# FranKinksTides.net
KiCad netlist of a schematic drawn in EAGLE
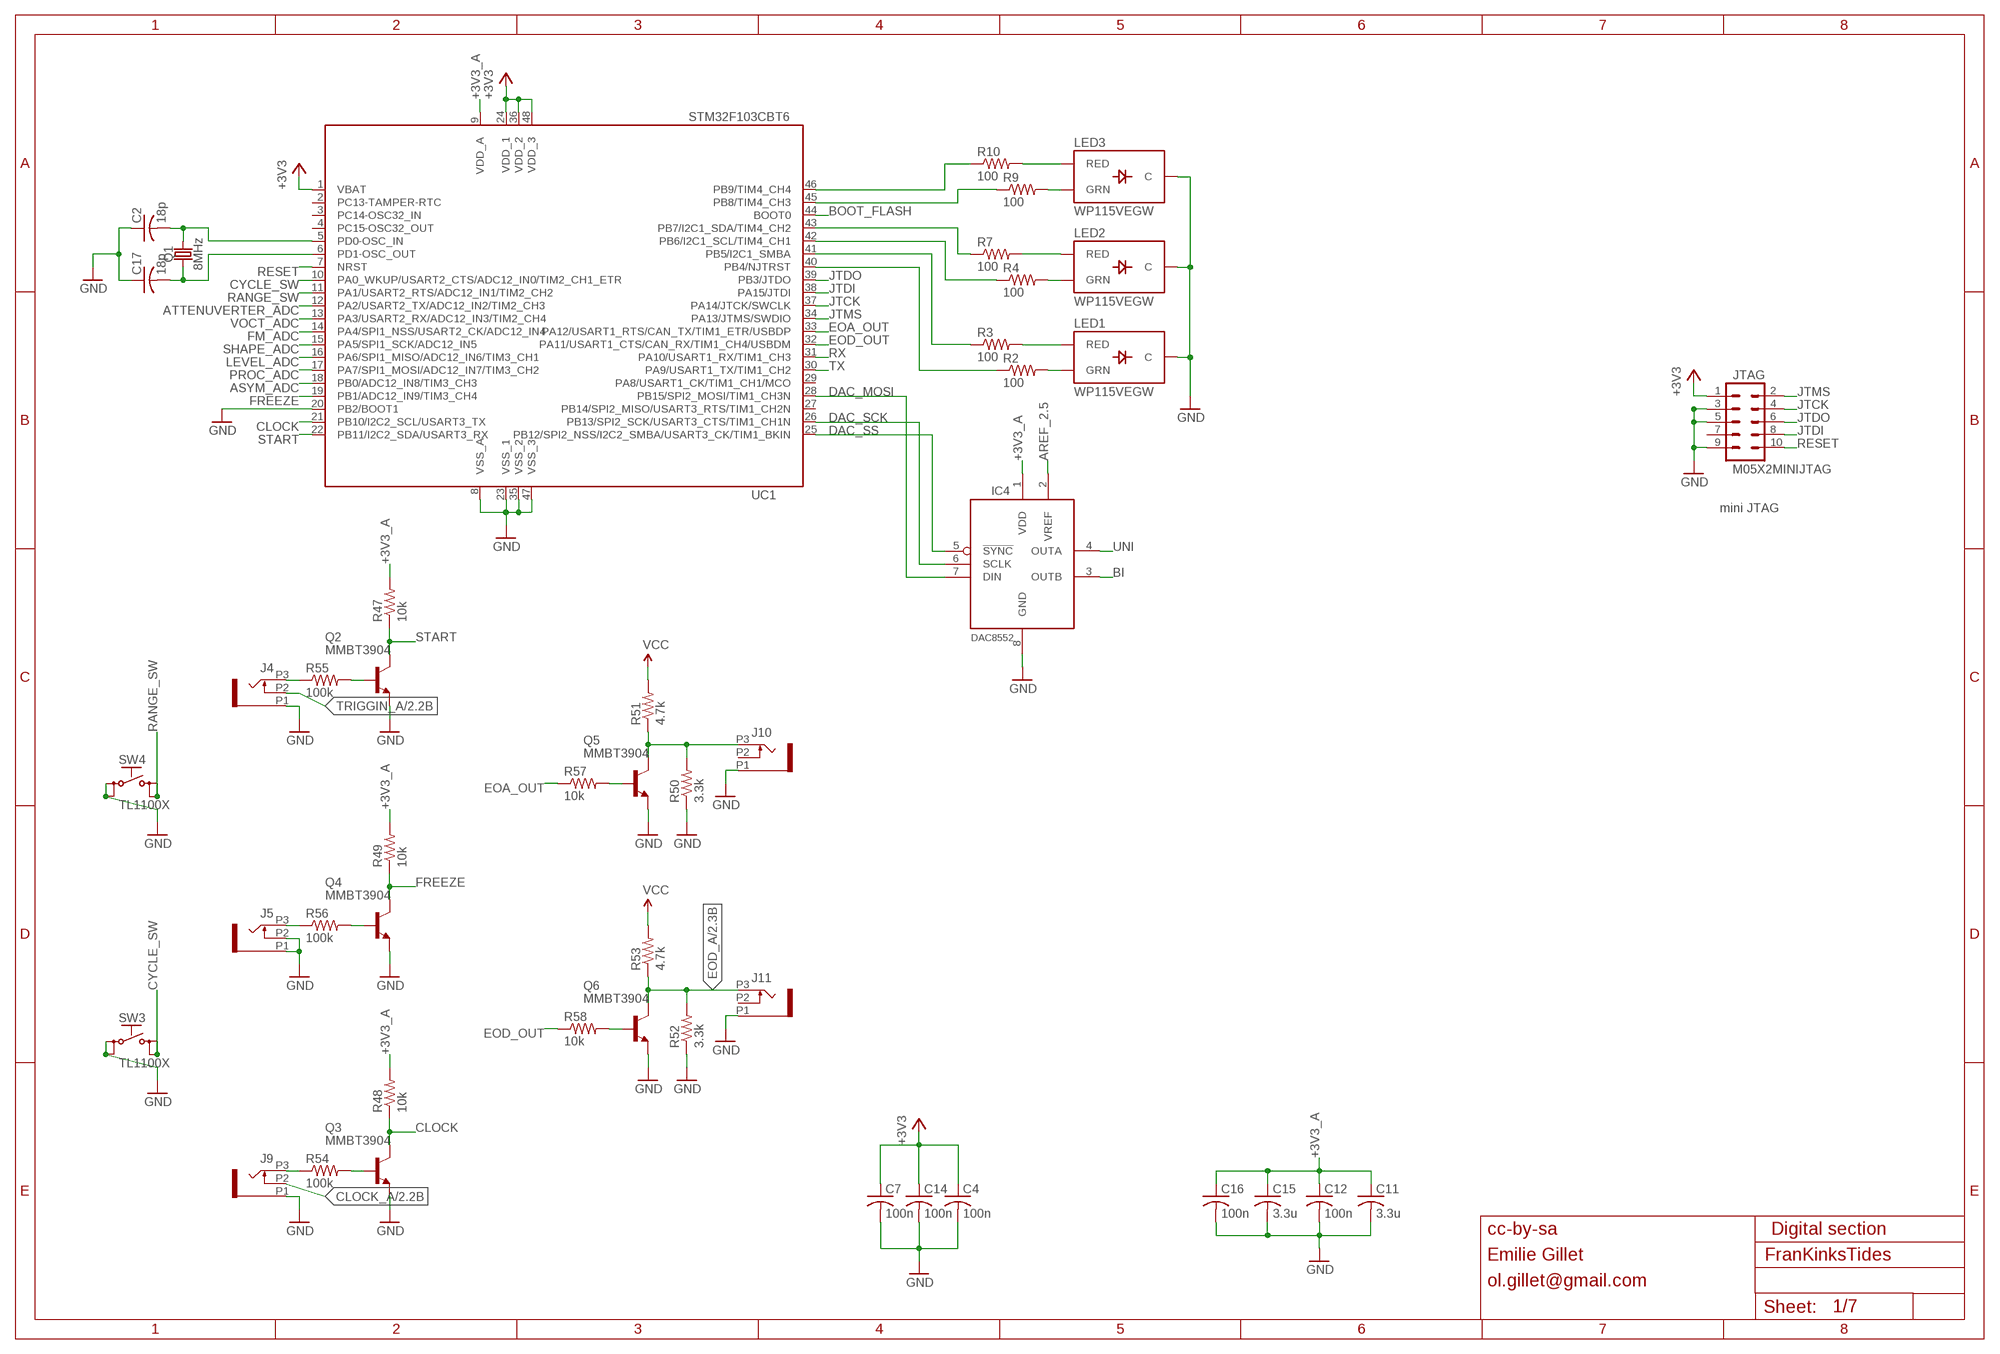
[diagram p0: schematic, sheet 1]
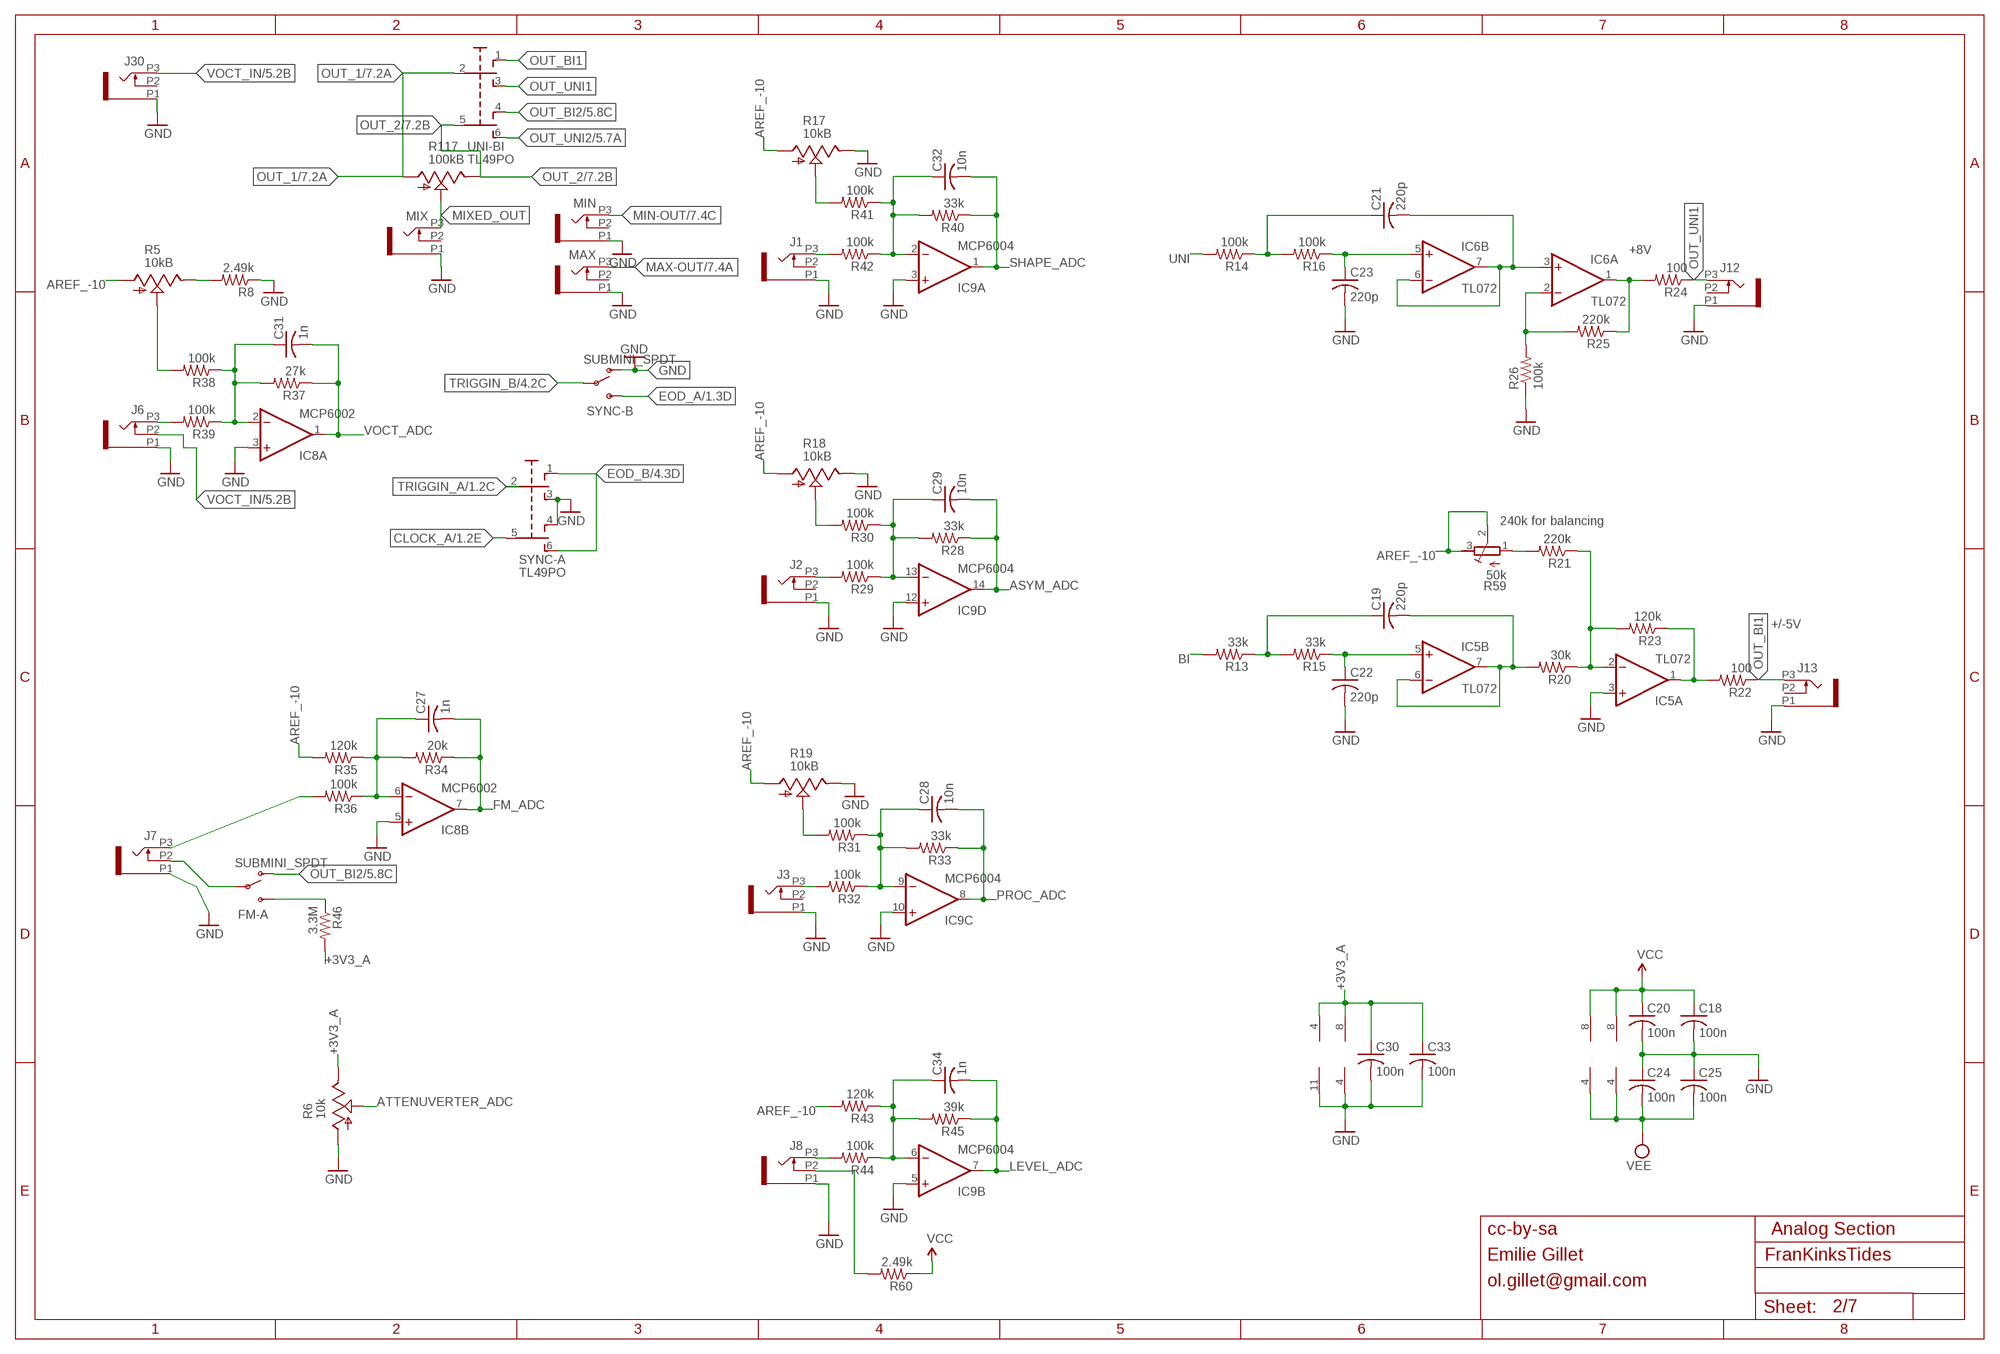
[diagram p1: schematic, sheet 2]
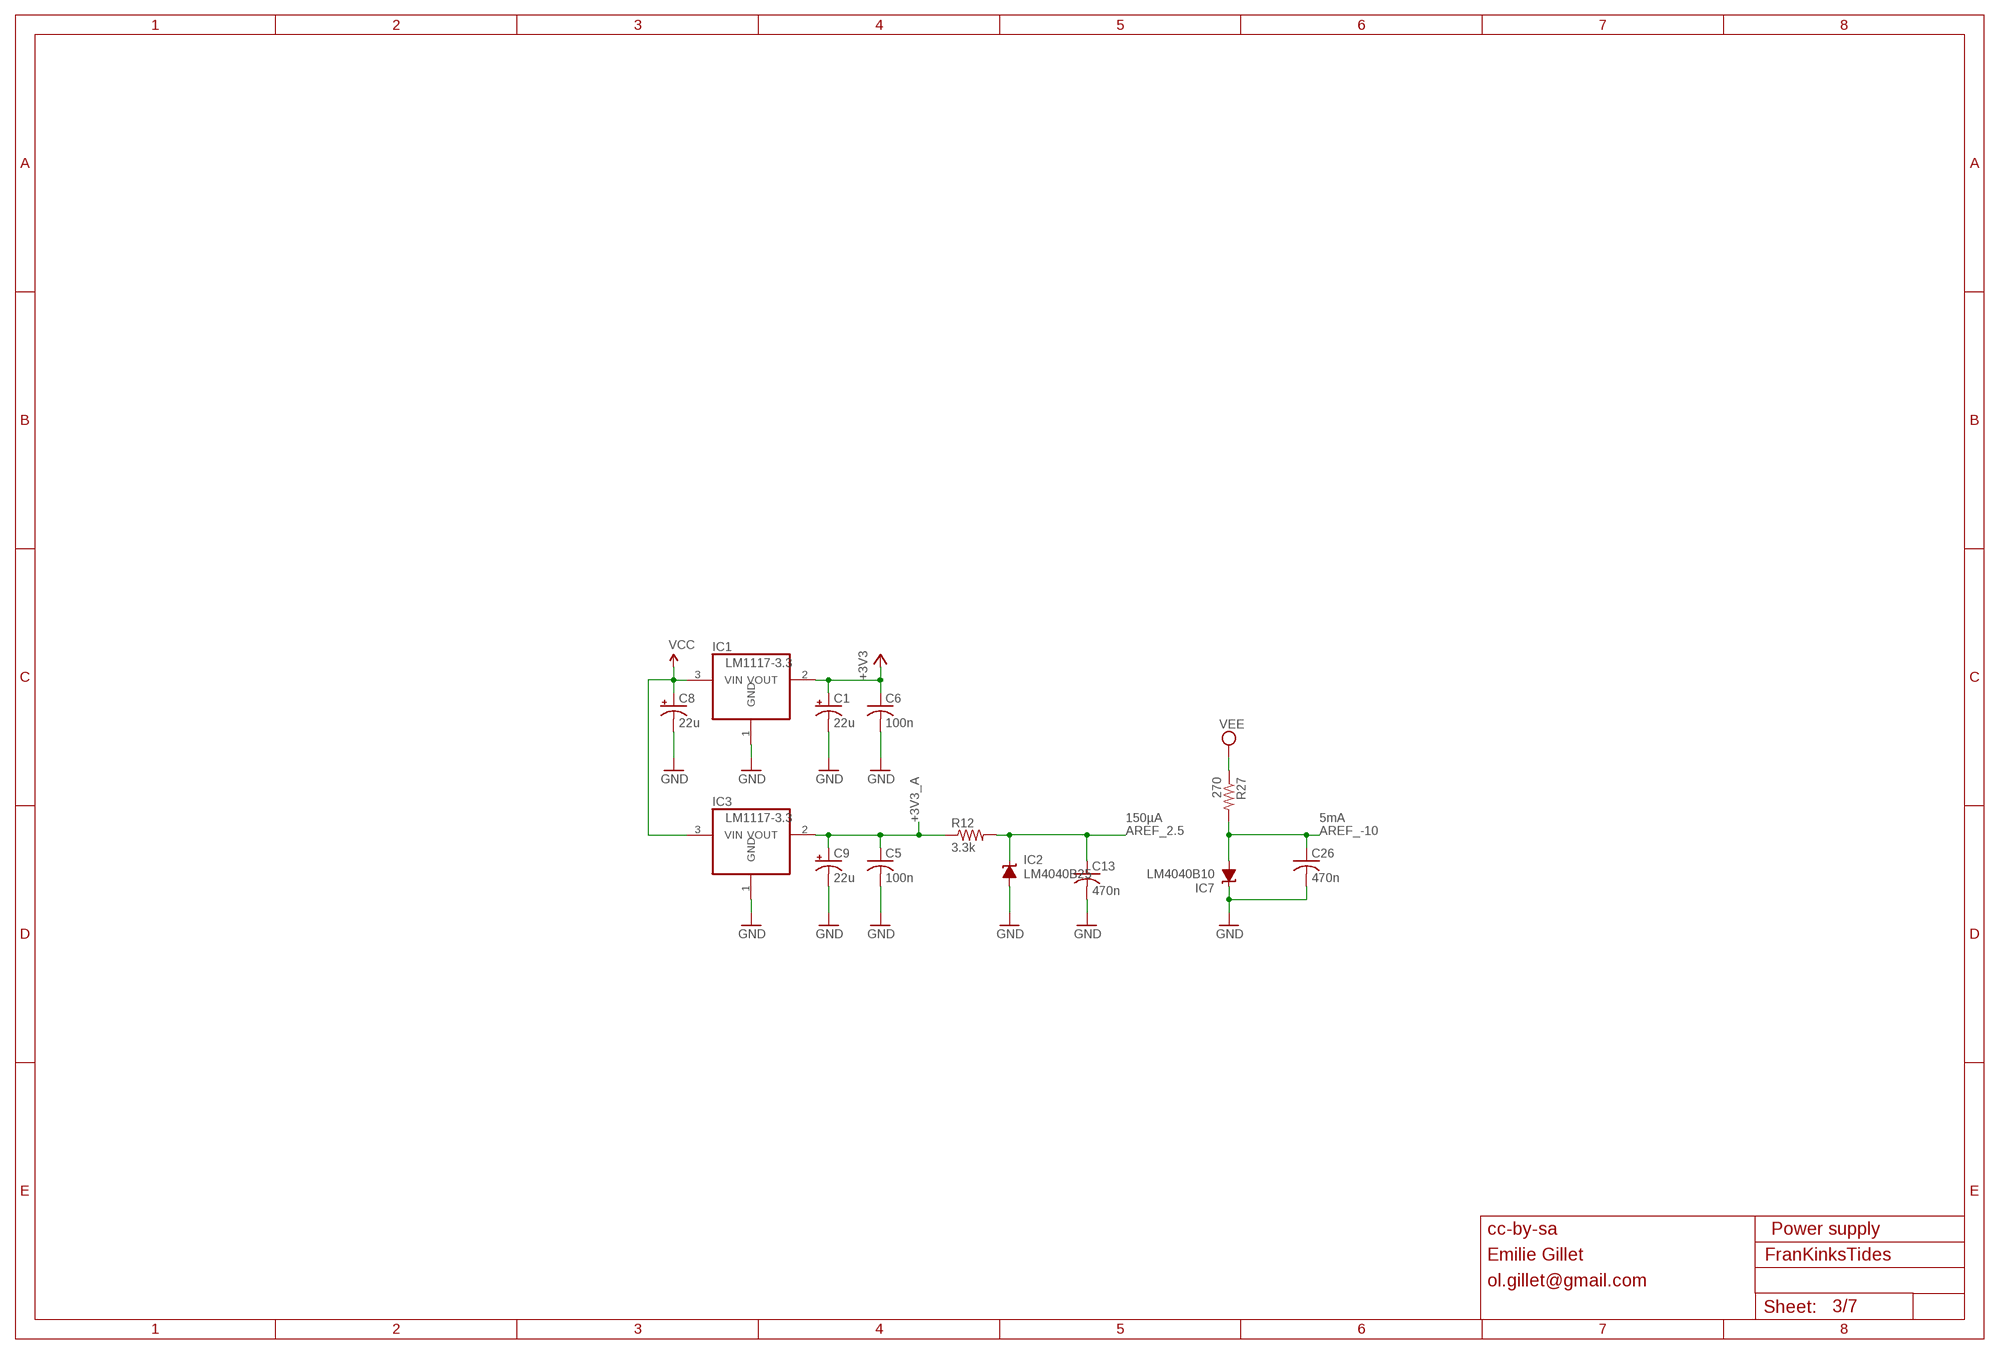
[diagram p2: schematic, sheet 3]
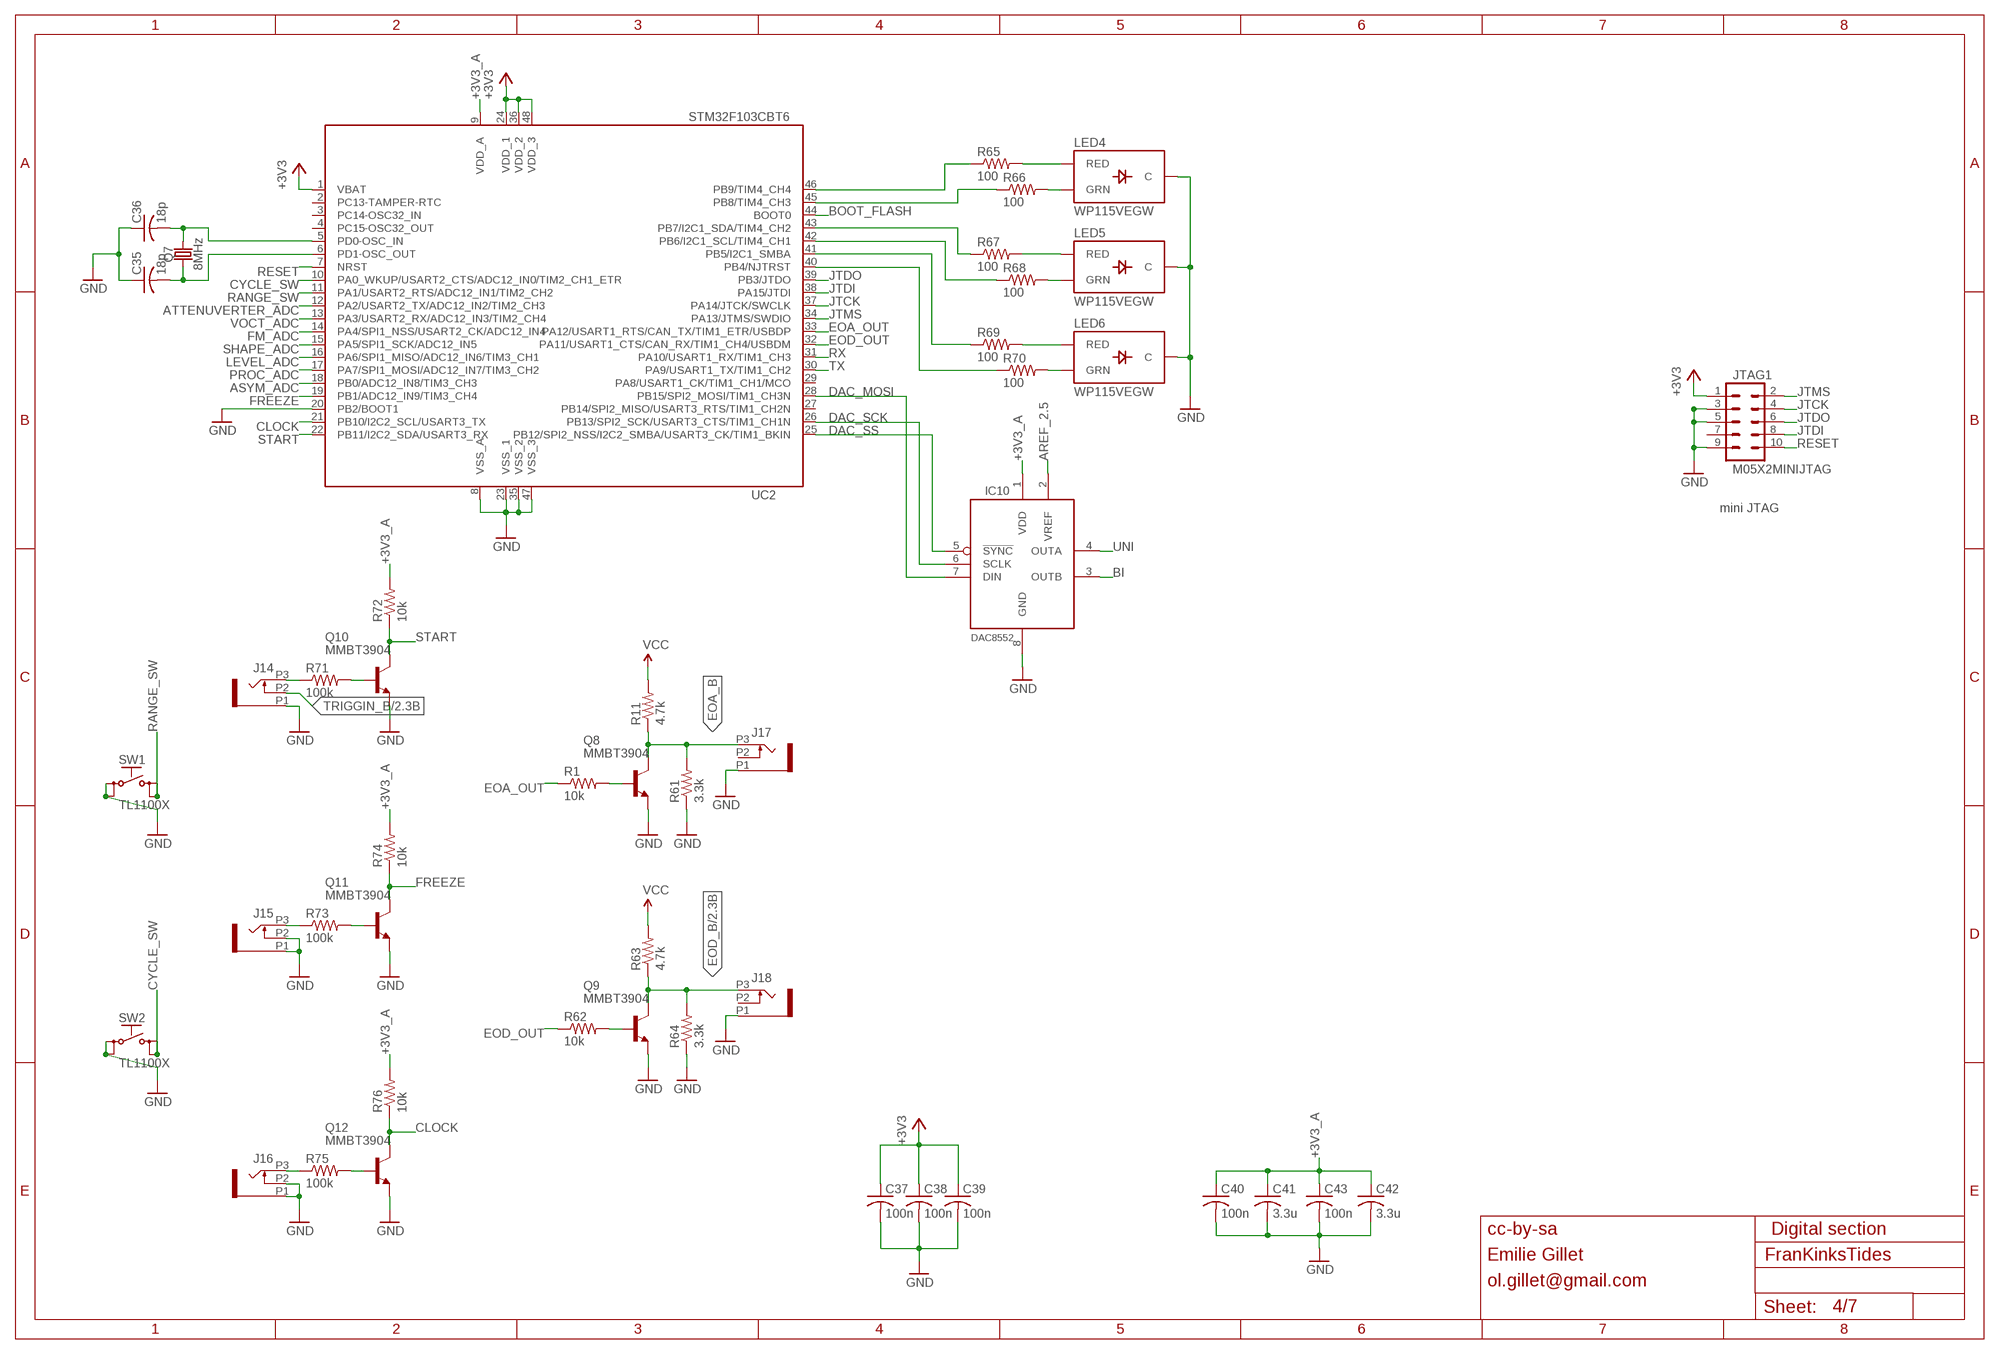
[diagram p3: schematic, sheet 4]
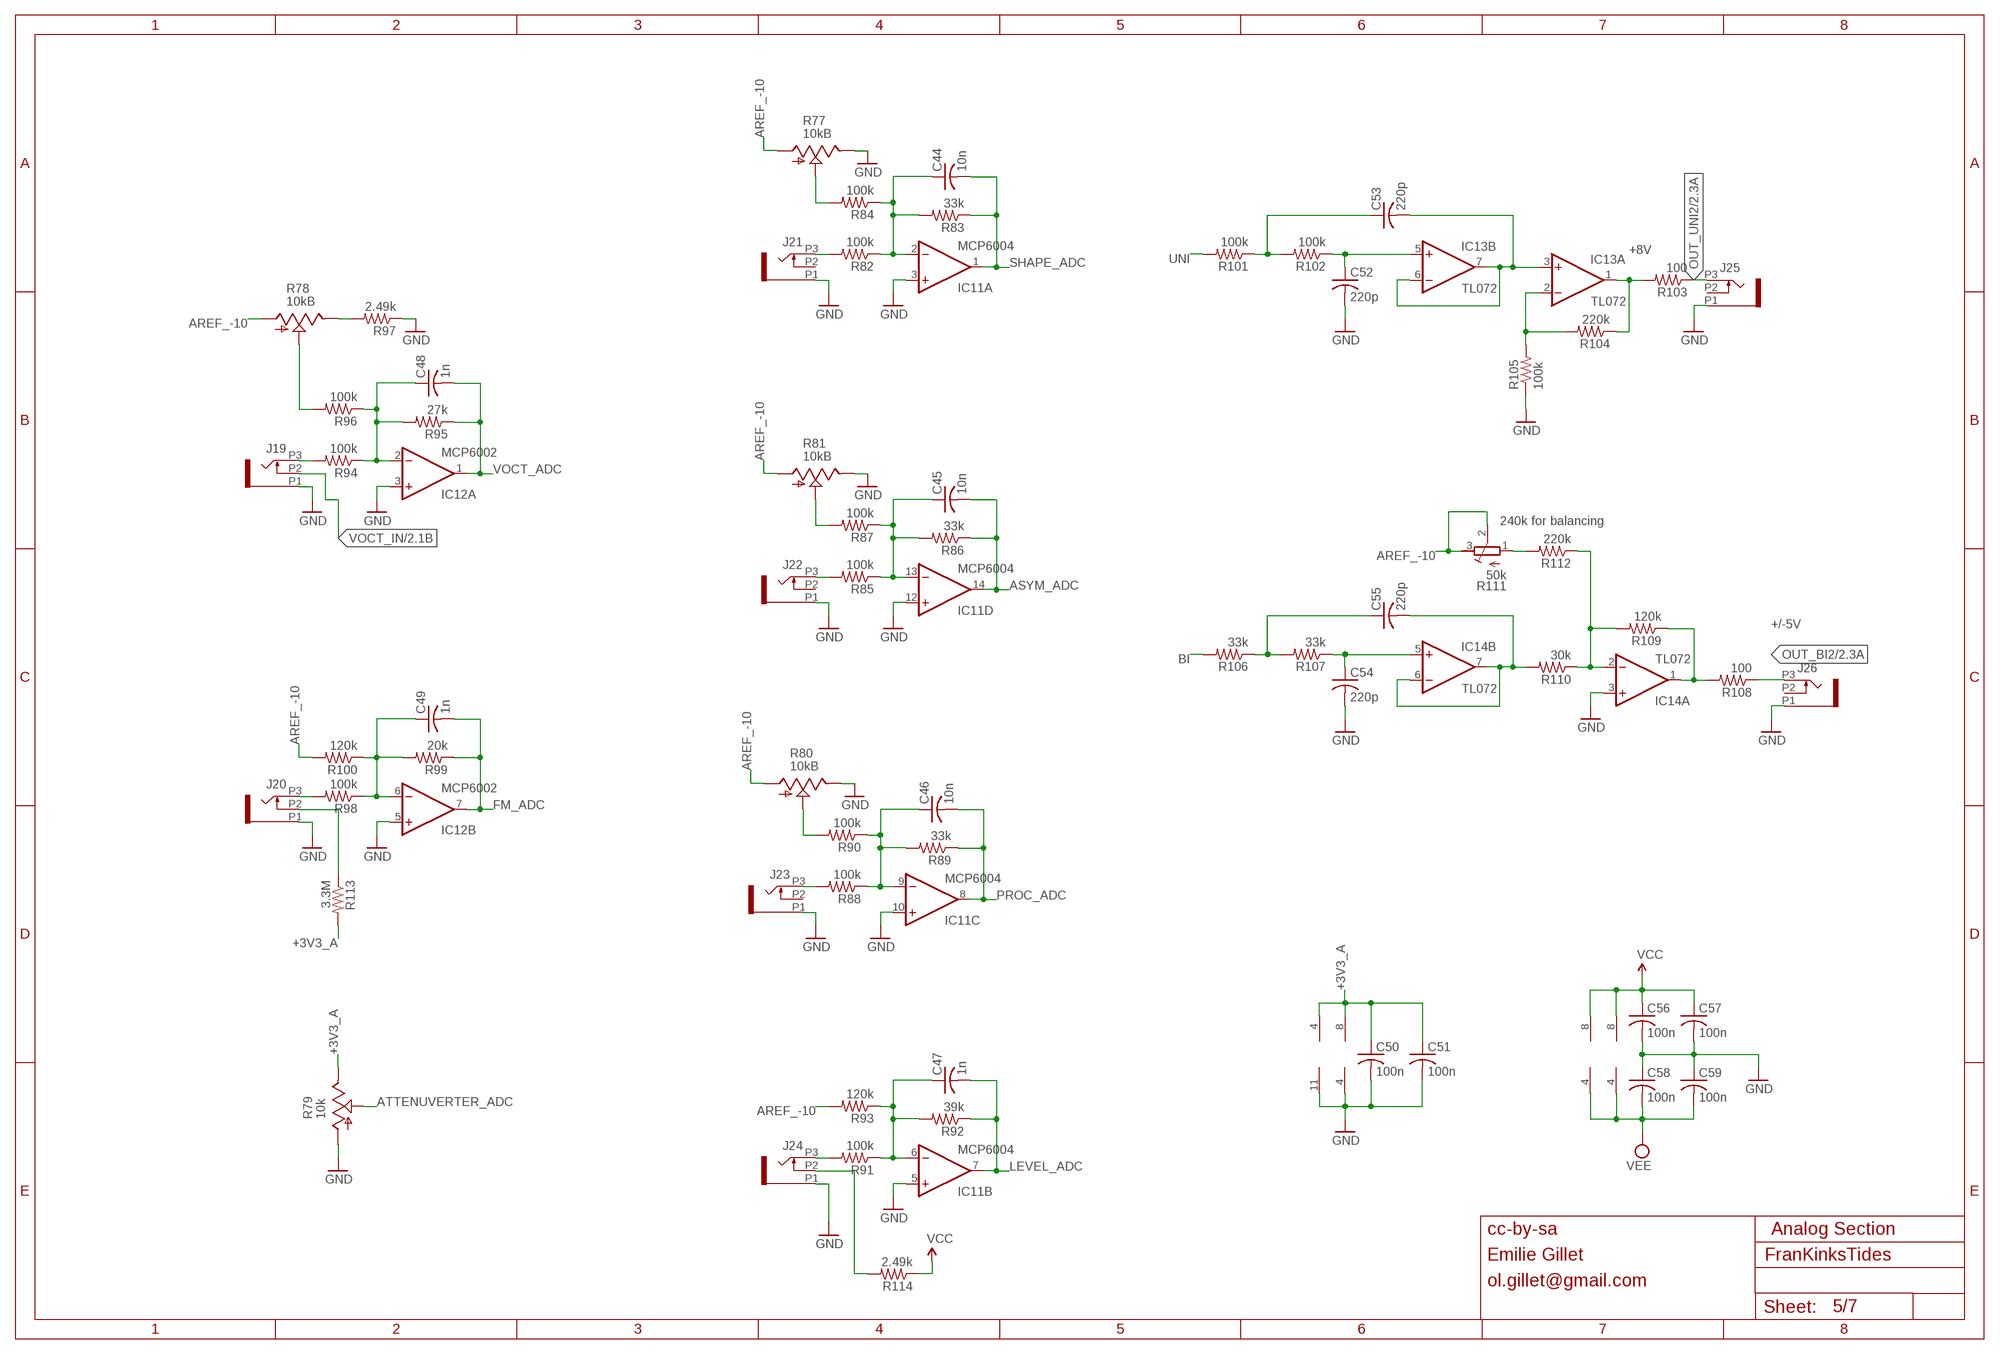
[diagram p4: schematic, sheet 5]
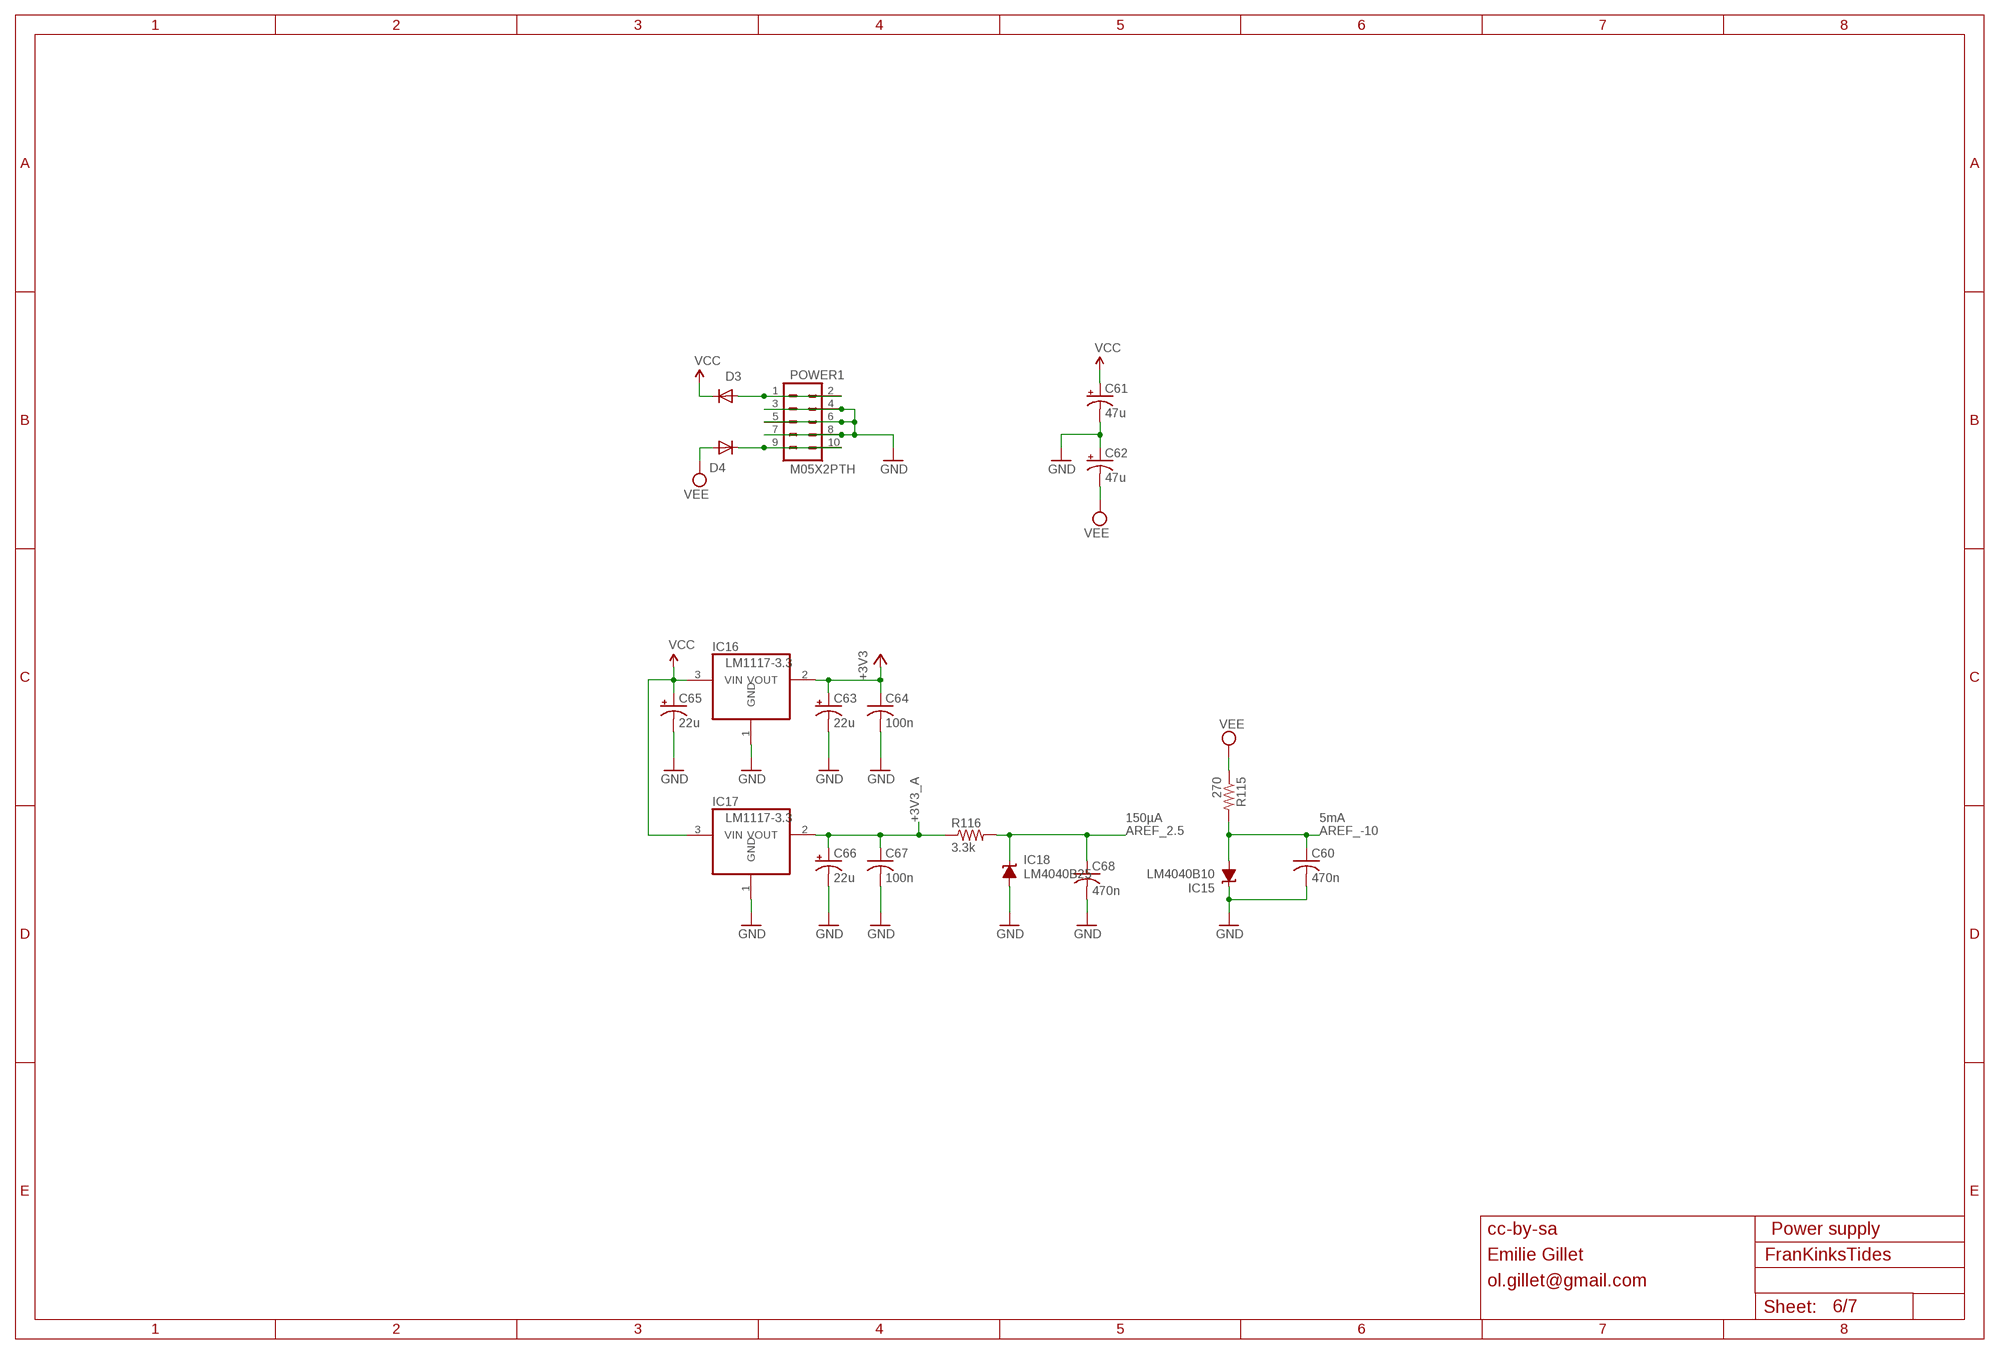
[diagram p5: schematic, sheet 6]
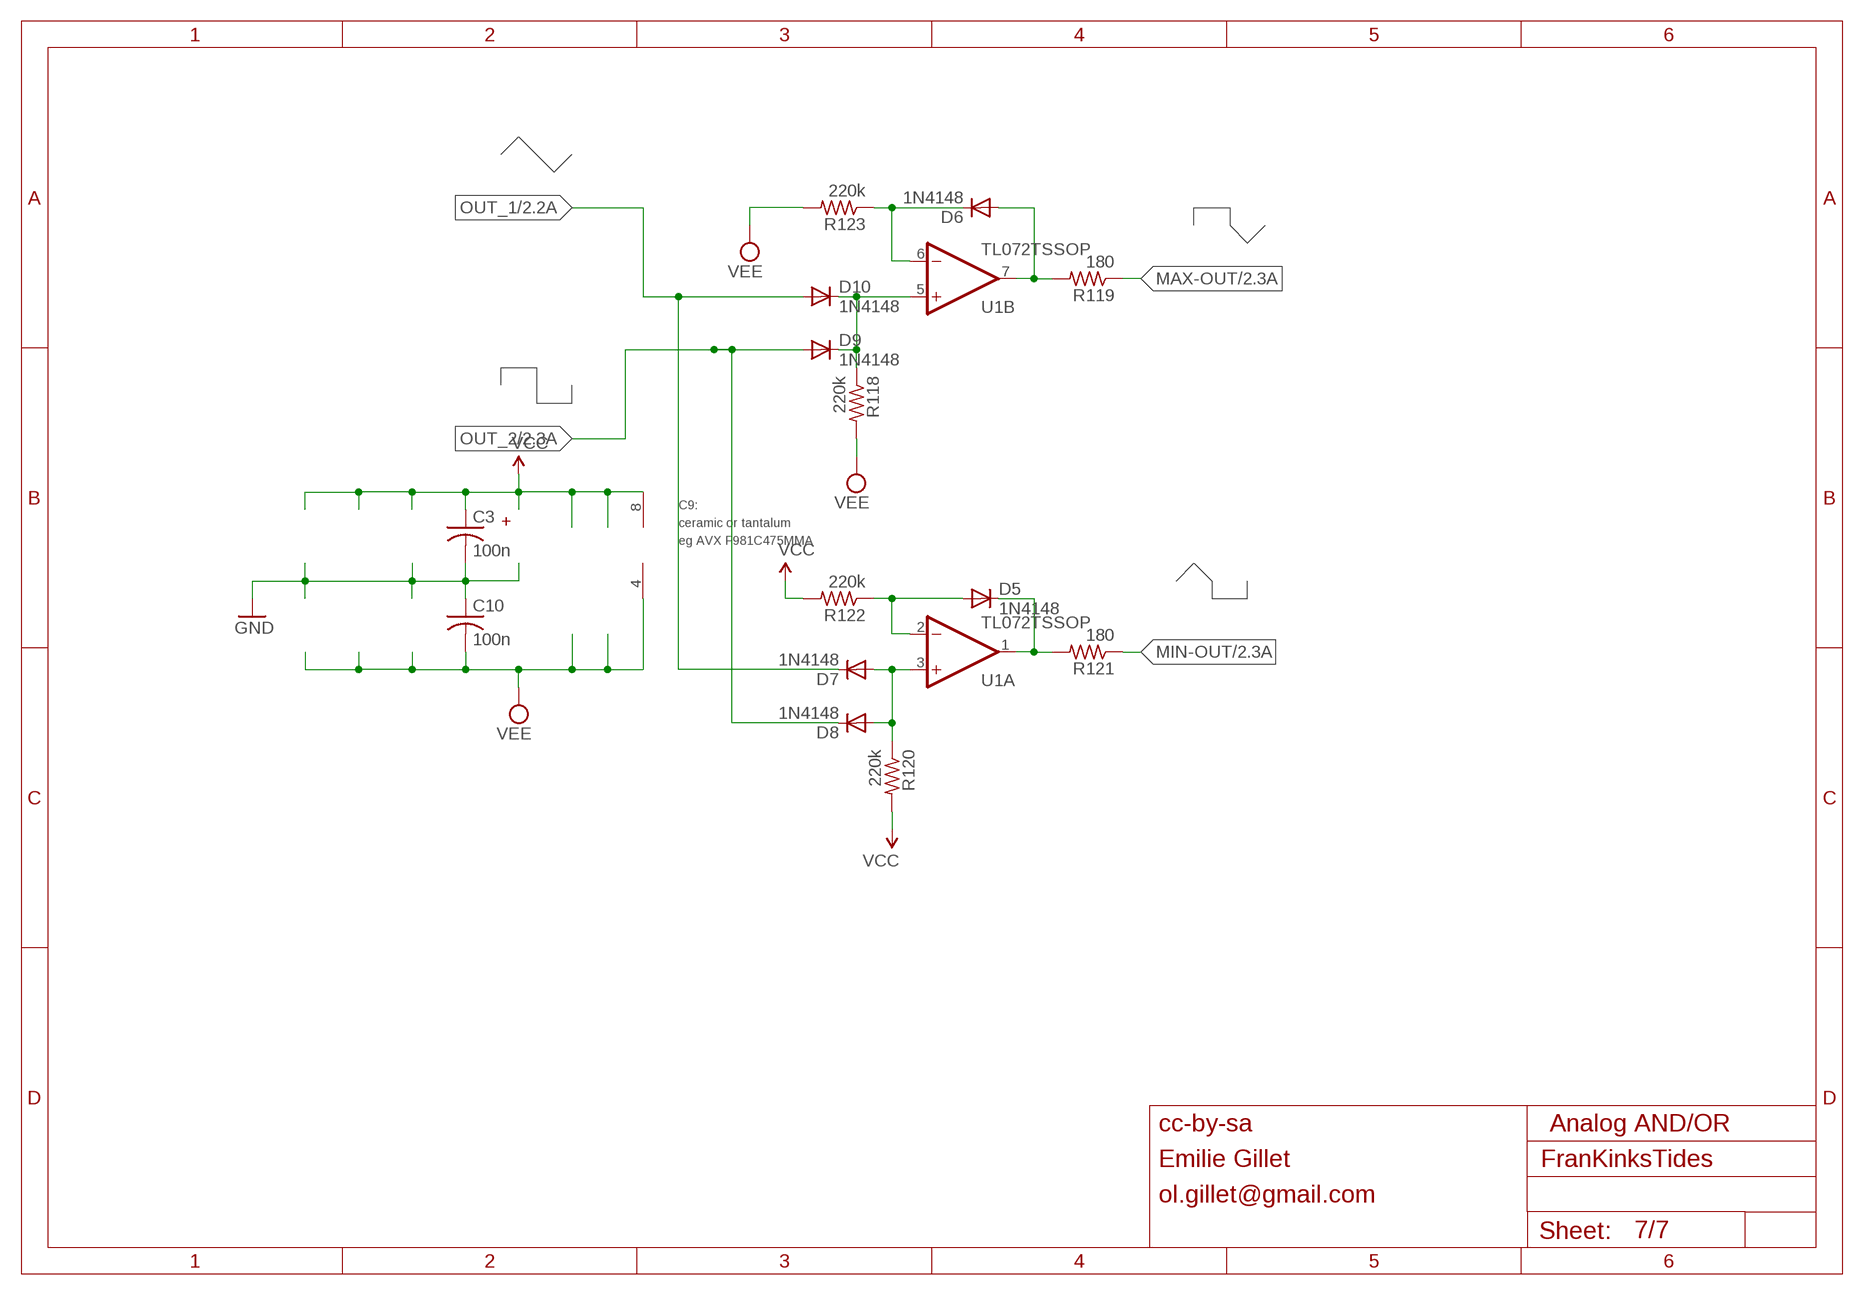
[diagram p6: schematic, sheet 7]

(export (version "E")
  (design (tool "Eeschema 10.0.6"))
  (components
    (comp (ref "C1")
      (value "22u")
      (footprint "eagle-import:PANASONIC_C")
      (libsource (lib "eagle-import") (part "CPOL-USC"))
    )
    (comp (ref "C5")
      (value "100n")
      (footprint "eagle-import:C0603")
      (libsource (lib "eagle-import") (part "C-USC0603"))
    )
    (comp (ref "C6")
      (value "100n")
      (footprint "eagle-import:C0603")
      (libsource (lib "eagle-import") (part "C-USC0603"))
    )
    (comp (ref "C8")
      (value "22u")
      (footprint "eagle-import:PANASONIC_C")
      (libsource (lib "eagle-import") (part "CPOL-USC"))
    )
    (comp (ref "C9")
      (value "22u")
      (footprint "eagle-import:PANASONIC_C")
      (libsource (lib "eagle-import") (part "CPOL-USC"))
    )
    (comp (ref "C13")
      (value "470n")
      (footprint "eagle-import:C0603")
      (libsource (lib "eagle-import") (part "C-USC0603"))
    )
    (comp (ref "C26")
      (value "470n")
      (footprint "eagle-import:C0603")
      (libsource (lib "eagle-import") (part "C-USC0603"))
    )
    (comp (ref "IC1")
      (value "LM1117-3.3")
      (footprint "eagle-import:SOT223")
      (libsource (lib "eagle-import") (part "REG1117"))
    )
    (comp (ref "IC2")
      (value "LM4040B25")
      (footprint "eagle-import:DBZ_R-PDSO-G3")
      (libsource (lib "eagle-import") (part "LM4041DBZB12"))
    )
    (comp (ref "IC3")
      (value "LM1117-3.3")
      (footprint "eagle-import:SOT223")
      (libsource (lib "eagle-import") (part "REG1117"))
    )
    (comp (ref "IC7")
      (value "LM4040B10")
      (footprint "eagle-import:DBZ_R-PDSO-G3")
      (libsource (lib "eagle-import") (part "LM4041DBZB12"))
    )
    (comp (ref "R12")
      (value "3.3k")
      (footprint "eagle-import:R0603")
      (libsource (lib "eagle-import") (part "R-US_R0603"))
    )
    (comp (ref "R27")
      (value "270")
      (footprint "eagle-import:R0603")
      (libsource (lib "eagle-import") (part "R-US_R0603"))
    )
    (comp (ref "C35")
      (value "18p")
      (footprint "eagle-import:C0603")
      (libsource (lib "eagle-import") (part "C-USC0603"))
    )
    (comp (ref "C36")
      (value "18p")
      (footprint "eagle-import:C0603")
      (libsource (lib "eagle-import") (part "C-USC0603"))
    )
    (comp (ref "C37")
      (value "100n")
      (footprint "eagle-import:C0603")
      (libsource (lib "eagle-import") (part "C-USC0603"))
    )
    (comp (ref "C38")
      (value "100n")
      (footprint "eagle-import:C0603")
      (libsource (lib "eagle-import") (part "C-USC0603"))
    )
    (comp (ref "C39")
      (value "100n")
      (footprint "eagle-import:C0603")
      (libsource (lib "eagle-import") (part "C-USC0603"))
    )
    (comp (ref "C40")
      (value "100n")
      (footprint "eagle-import:C0603")
      (libsource (lib "eagle-import") (part "C-USC0603"))
    )
    (comp (ref "C41")
      (value "3.3u")
      (footprint "eagle-import:C0603")
      (libsource (lib "eagle-import") (part "C-USC0603"))
    )
    (comp (ref "C42")
      (value "3.3u")
      (footprint "eagle-import:C0603")
      (libsource (lib "eagle-import") (part "C-USC0603"))
    )
    (comp (ref "C43")
      (value "100n")
      (footprint "eagle-import:C0603")
      (libsource (lib "eagle-import") (part "C-USC0603"))
    )
    (comp (ref "IC10")
      (value "DAC8552")
      (footprint "eagle-import:MSOP-8")
      (libsource (lib "eagle-import") (part "DAC8552"))
    )
    (comp (ref "J14")
      (value "PJ301_GUI6")
      (footprint "eagle-import:OG-PJ301_VARIATIONS_WQP_PJ_301M6")
      (libsource (lib "eagle-import") (part "PJ301_GUI6"))
    )
    (comp (ref "J15")
      (value "PJ301_GUI6")
      (footprint "eagle-import:OG-PJ301_VARIATIONS_WQP_PJ_301M6")
      (libsource (lib "eagle-import") (part "PJ301_GUI6"))
    )
    (comp (ref "J16")
      (value "PJ301_GUI6")
      (footprint "eagle-import:OG-PJ301_VARIATIONS_WQP_PJ_301M6")
      (libsource (lib "eagle-import") (part "PJ301_GUI6"))
    )
    (comp (ref "J17")
      (value "PJ301_GUI6")
      (footprint "eagle-import:OG-PJ301_VARIATIONS_WQP_PJ_301M6")
      (libsource (lib "eagle-import") (part "PJ301_GUI6"))
    )
    (comp (ref "J18")
      (value "PJ301_GUI6")
      (footprint "eagle-import:OG-PJ301_VARIATIONS_WQP_PJ_301M6")
      (libsource (lib "eagle-import") (part "PJ301_GUI6"))
    )
    (comp (ref "JTAG1")
      (value "M05X2MINIJTAG")
      (footprint "eagle-import:2X5-1.27")
      (libsource (lib "eagle-import") (part "M05X2MINIJTAG"))
    )
    (comp (ref "LED4")
      (value "WP115VEGW")
      (footprint "eagle-import:LED-BICOLOR-THROUGHHOLE")
      (libsource (lib "eagle-import") (part "LED-BICOLOR-THROUGHHOLE"))
    )
    (comp (ref "LED5")
      (value "WP115VEGW")
      (footprint "eagle-import:LED-BICOLOR-THROUGHHOLE")
      (libsource (lib "eagle-import") (part "LED-BICOLOR-THROUGHHOLE"))
    )
    (comp (ref "LED6")
      (value "WP115VEGW")
      (footprint "eagle-import:LED-BICOLOR-THROUGHHOLE")
      (libsource (lib "eagle-import") (part "LED-BICOLOR-THROUGHHOLE"))
    )
    (comp (ref "Q7")
      (value "8MHz")
      (footprint "eagle-import:HC49UP")
      (libsource (lib "eagle-import") (part "CRYSTAL-8MHZSMD-HC49UP"))
    )
    (comp (ref "Q8")
      (value "MMBT3904")
      (footprint "eagle-import:SOT23-BEC")
      (libsource (lib "eagle-import") (part "-NPN-SOT23-BECMMBT3904LT1"))
    )
    (comp (ref "Q9")
      (value "MMBT3904")
      (footprint "eagle-import:SOT23-BEC")
      (libsource (lib "eagle-import") (part "-NPN-SOT23-BECMMBT3904LT1"))
    )
    (comp (ref "Q10")
      (value "MMBT3904")
      (footprint "eagle-import:SOT23-BEC")
      (libsource (lib "eagle-import") (part "-NPN-SOT23-BECMMBT3904LT1"))
    )
    (comp (ref "Q11")
      (value "MMBT3904")
      (footprint "eagle-import:SOT23-BEC")
      (libsource (lib "eagle-import") (part "-NPN-SOT23-BECMMBT3904LT1"))
    )
    (comp (ref "Q12")
      (value "MMBT3904")
      (footprint "eagle-import:SOT23-BEC")
      (libsource (lib "eagle-import") (part "-NPN-SOT23-BECMMBT3904LT1"))
    )
    (comp (ref "R1")
      (value "10k")
      (footprint "eagle-import:R0603")
      (libsource (lib "eagle-import") (part "R-US_R0603"))
    )
    (comp (ref "R11")
      (value "4.7k")
      (footprint "eagle-import:R0603")
      (libsource (lib "eagle-import") (part "R-US_R0603"))
    )
    (comp (ref "R61")
      (value "3.3k")
      (footprint "eagle-import:R0603")
      (libsource (lib "eagle-import") (part "R-US_R0603"))
    )
    (comp (ref "R62")
      (value "10k")
      (footprint "eagle-import:R0603")
      (libsource (lib "eagle-import") (part "R-US_R0603"))
    )
    (comp (ref "R63")
      (value "4.7k")
      (footprint "eagle-import:R0603")
      (libsource (lib "eagle-import") (part "R-US_R0603"))
    )
    (comp (ref "R64")
      (value "3.3k")
      (footprint "eagle-import:R0603")
      (libsource (lib "eagle-import") (part "R-US_R0603"))
    )
    (comp (ref "R65")
      (value "100")
      (footprint "eagle-import:R0603")
      (libsource (lib "eagle-import") (part "R-US_R0603"))
    )
    (comp (ref "R66")
      (value "100")
      (footprint "eagle-import:R0603")
      (libsource (lib "eagle-import") (part "R-US_R0603"))
    )
    (comp (ref "R67")
      (value "100")
      (footprint "eagle-import:R0603")
      (libsource (lib "eagle-import") (part "R-US_R0603"))
    )
    (comp (ref "R68")
      (value "100")
      (footprint "eagle-import:R0603")
      (libsource (lib "eagle-import") (part "R-US_R0603"))
    )
    (comp (ref "R69")
      (value "100")
      (footprint "eagle-import:R0603")
      (libsource (lib "eagle-import") (part "R-US_R0603"))
    )
    (comp (ref "R70")
      (value "100")
      (footprint "eagle-import:R0603")
      (libsource (lib "eagle-import") (part "R-US_R0603"))
    )
    (comp (ref "R71")
      (value "100k")
      (footprint "eagle-import:R0603")
      (libsource (lib "eagle-import") (part "R-US_R0603"))
    )
    (comp (ref "R72")
      (value "10k")
      (footprint "eagle-import:R0603")
      (libsource (lib "eagle-import") (part "R-US_R0603"))
    )
    (comp (ref "R73")
      (value "100k")
      (footprint "eagle-import:R0603")
      (libsource (lib "eagle-import") (part "R-US_R0603"))
    )
    (comp (ref "R74")
      (value "10k")
      (footprint "eagle-import:R0603")
      (libsource (lib "eagle-import") (part "R-US_R0603"))
    )
    (comp (ref "R75")
      (value "100k")
      (footprint "eagle-import:R0603")
      (libsource (lib "eagle-import") (part "R-US_R0603"))
    )
    (comp (ref "R76")
      (value "10k")
      (footprint "eagle-import:R0603")
      (libsource (lib "eagle-import") (part "R-US_R0603"))
    )
    (comp (ref "SW1")
      (value "TL1100X")
      (footprint "eagle-import:TL1100X")
      (libsource (lib "eagle-import") (part "TL1100X"))
    )
    (comp (ref "SW2")
      (value "TL1100X")
      (footprint "eagle-import:TL1100X")
      (libsource (lib "eagle-import") (part "TL1100X"))
    )
    (comp (ref "UC2")
      (value "STM32F103CBT6")
      (footprint "eagle-import:LQFP48")
      (libsource (lib "eagle-import") (part "STM32F103CB"))
    )
    (comp (ref "C44")
      (value "10n")
      (footprint "eagle-import:C0603")
      (libsource (lib "eagle-import") (part "C-USC0603"))
    )
    (comp (ref "C45")
      (value "10n")
      (footprint "eagle-import:C0603")
      (libsource (lib "eagle-import") (part "C-USC0603"))
    )
    (comp (ref "C46")
      (value "10n")
      (footprint "eagle-import:C0603")
      (libsource (lib "eagle-import") (part "C-USC0603"))
    )
    (comp (ref "C47")
      (value "1n")
      (footprint "eagle-import:C0603")
      (libsource (lib "eagle-import") (part "C-USC0603"))
    )
    (comp (ref "C48")
      (value "1n")
      (footprint "eagle-import:C0603")
      (libsource (lib "eagle-import") (part "C-USC0603"))
    )
    (comp (ref "C49")
      (value "1n")
      (footprint "eagle-import:C0603")
      (libsource (lib "eagle-import") (part "C-USC0603"))
    )
    (comp (ref "C50")
      (value "100n")
      (footprint "eagle-import:C0603")
      (libsource (lib "eagle-import") (part "C-USC0603"))
    )
    (comp (ref "C51")
      (value "100n")
      (footprint "eagle-import:C0603")
      (libsource (lib "eagle-import") (part "C-USC0603"))
    )
    (comp (ref "C52")
      (value "220p")
      (footprint "eagle-import:C0603")
      (libsource (lib "eagle-import") (part "C-USC0603"))
    )
    (comp (ref "C53")
      (value "220p")
      (footprint "eagle-import:C0603")
      (libsource (lib "eagle-import") (part "C-USC0603"))
    )
    (comp (ref "C54")
      (value "220p")
      (footprint "eagle-import:C0603")
      (libsource (lib "eagle-import") (part "C-USC0603"))
    )
    (comp (ref "C55")
      (value "220p")
      (footprint "eagle-import:C0603")
      (libsource (lib "eagle-import") (part "C-USC0603"))
    )
    (comp (ref "C56")
      (value "100n")
      (footprint "eagle-import:C0603")
      (libsource (lib "eagle-import") (part "C-USC0603"))
    )
    (comp (ref "C57")
      (value "100n")
      (footprint "eagle-import:C0603")
      (libsource (lib "eagle-import") (part "C-USC0603"))
    )
    (comp (ref "C58")
      (value "100n")
      (footprint "eagle-import:C0603")
      (libsource (lib "eagle-import") (part "C-USC0603"))
    )
    (comp (ref "C59")
      (value "100n")
      (footprint "eagle-import:C0603")
      (libsource (lib "eagle-import") (part "C-USC0603"))
    )
    (comp (ref "IC11")
      (value "MCP6004")
      (footprint "eagle-import:TSSOP14")
      (libsource (lib "eagle-import") (part "MCP6004ST"))
    )
    (comp (ref "IC12")
      (value "MCP6002")
      (footprint "eagle-import:SO08")
      (libsource (lib "eagle-import") (part "TL072D"))
    )
    (comp (ref "IC13")
      (value "TL072")
      (footprint "eagle-import:TSSOP-8")
      (libsource (lib "eagle-import") (part "MusicThingModular_TL072TSSOP"))
    )
    (comp (ref "IC14")
      (value "TL072")
      (footprint "eagle-import:TSSOP-8")
      (libsource (lib "eagle-import") (part "MusicThingModular_TL072TSSOP"))
    )
    (comp (ref "J19")
      (value "PJ301_GUI6")
      (footprint "eagle-import:OG-PJ301_VARIATIONS_WQP_PJ_301M6")
      (libsource (lib "eagle-import") (part "PJ301_GUI6"))
    )
    (comp (ref "J20")
      (value "PJ301_GUI6")
      (footprint "eagle-import:OG-PJ301_VARIATIONS_WQP_PJ_301M6")
      (libsource (lib "eagle-import") (part "PJ301_GUI6"))
    )
    (comp (ref "J21")
      (value "PJ301_GUI6")
      (footprint "eagle-import:OG-PJ301_VARIATIONS_WQP_PJ_301M6")
      (libsource (lib "eagle-import") (part "PJ301_GUI6"))
    )
    (comp (ref "J22")
      (value "PJ301_GUI6")
      (footprint "eagle-import:OG-PJ301_VARIATIONS_WQP_PJ_301M6")
      (libsource (lib "eagle-import") (part "PJ301_GUI6"))
    )
    (comp (ref "J23")
      (value "PJ301_GUI6")
      (footprint "eagle-import:OG-PJ301_VARIATIONS_WQP_PJ_301M6")
      (libsource (lib "eagle-import") (part "PJ301_GUI6"))
    )
    (comp (ref "J24")
      (value "PJ301_GUI6")
      (footprint "eagle-import:OG-PJ301_VARIATIONS_WQP_PJ_301M6")
      (libsource (lib "eagle-import") (part "PJ301_GUI6"))
    )
    (comp (ref "J25")
      (value "PJ301_GUI6")
      (footprint "eagle-import:OG-PJ301_VARIATIONS_WQP_PJ_301M6")
      (libsource (lib "eagle-import") (part "PJ301_GUI6"))
    )
    (comp (ref "J26")
      (value "PJ301_GUI6")
      (footprint "eagle-import:OG-PJ301_VARIATIONS_WQP_PJ_301M6")
      (libsource (lib "eagle-import") (part "PJ301_GUI6"))
    )
    (comp (ref "R77")
      (value "10kB")
      (footprint "eagle-import:TALLTRIMMER")
      (libsource (lib "eagle-import") (part "POT-ALPS_POT_US"))
    )
    (comp (ref "R78")
      (value "10kB")
      (footprint "eagle-import:ALPS_POT_VERTICAL_PS")
      (libsource (lib "eagle-import") (part "POT_USVERTICAL_PS"))
    )
    (comp (ref "R79")
      (value "10k")
      (footprint "eagle-import:TALLTRIMMER")
      (libsource (lib "eagle-import") (part "POT-ALPS_POT_US"))
    )
    (comp (ref "R80")
      (value "10kB")
      (footprint "eagle-import:TALLTRIMMER")
      (libsource (lib "eagle-import") (part "POT-ALPS_POT_US"))
    )
    (comp (ref "R81")
      (value "10kB")
      (footprint "eagle-import:TALLTRIMMER")
      (libsource (lib "eagle-import") (part "POT-ALPS_POT_US"))
    )
    (comp (ref "R82")
      (value "100k")
      (footprint "eagle-import:R0603")
      (libsource (lib "eagle-import") (part "R-US_R0603"))
    )
    (comp (ref "R83")
      (value "33k")
      (footprint "eagle-import:R0603")
      (libsource (lib "eagle-import") (part "R-US_R0603"))
    )
    (comp (ref "R84")
      (value "100k")
      (footprint "eagle-import:R0603")
      (libsource (lib "eagle-import") (part "R-US_R0603"))
    )
    (comp (ref "R85")
      (value "100k")
      (footprint "eagle-import:R0603")
      (libsource (lib "eagle-import") (part "R-US_R0603"))
    )
    (comp (ref "R86")
      (value "33k")
      (footprint "eagle-import:R0603")
      (libsource (lib "eagle-import") (part "R-US_R0603"))
    )
    (comp (ref "R87")
      (value "100k")
      (footprint "eagle-import:R0603")
      (libsource (lib "eagle-import") (part "R-US_R0603"))
    )
    (comp (ref "R88")
      (value "100k")
      (footprint "eagle-import:R0603")
      (libsource (lib "eagle-import") (part "R-US_R0603"))
    )
    (comp (ref "R89")
      (value "33k")
      (footprint "eagle-import:R0603")
      (libsource (lib "eagle-import") (part "R-US_R0603"))
    )
    (comp (ref "R90")
      (value "100k")
      (footprint "eagle-import:R0603")
      (libsource (lib "eagle-import") (part "R-US_R0603"))
    )
    (comp (ref "R91")
      (value "100k")
      (footprint "eagle-import:R0603")
      (libsource (lib "eagle-import") (part "R-US_R0603"))
    )
    (comp (ref "R92")
      (value "39k")
      (footprint "eagle-import:R0603")
      (libsource (lib "eagle-import") (part "R-US_R0603"))
    )
    (comp (ref "R93")
      (value "120k")
      (footprint "eagle-import:R0603")
      (libsource (lib "eagle-import") (part "R-US_R0603"))
    )
    (comp (ref "R94")
      (value "100k")
      (footprint "eagle-import:R0603")
      (libsource (lib "eagle-import") (part "R-US_R0603"))
    )
    (comp (ref "R95")
      (value "27k")
      (footprint "eagle-import:R0603")
      (libsource (lib "eagle-import") (part "R-US_R0603"))
    )
    (comp (ref "R96")
      (value "100k")
      (footprint "eagle-import:R0603")
      (libsource (lib "eagle-import") (part "R-US_R0603"))
    )
    (comp (ref "R97")
      (value "2.49k")
      (footprint "eagle-import:R0603")
      (libsource (lib "eagle-import") (part "R-US_R0603"))
    )
    (comp (ref "R98")
      (value "100k")
      (footprint "eagle-import:R0603")
      (libsource (lib "eagle-import") (part "R-US_R0603"))
    )
    (comp (ref "R99")
      (value "20k")
      (footprint "eagle-import:R0603")
      (libsource (lib "eagle-import") (part "R-US_R0603"))
    )
    (comp (ref "R100")
      (value "120k")
      (footprint "eagle-import:R0603")
      (libsource (lib "eagle-import") (part "R-US_R0603"))
    )
    (comp (ref "R101")
      (value "100k")
      (footprint "eagle-import:R0603")
      (libsource (lib "eagle-import") (part "R-US_R0603"))
    )
    (comp (ref "R102")
      (value "100k")
      (footprint "eagle-import:R0603")
      (libsource (lib "eagle-import") (part "R-US_R0603"))
    )
    (comp (ref "R103")
      (value "100")
      (footprint "eagle-import:R0603")
      (libsource (lib "eagle-import") (part "R-US_R0603"))
    )
    (comp (ref "R104")
      (value "220k")
      (footprint "eagle-import:R0603")
      (libsource (lib "eagle-import") (part "R-US_R0603"))
    )
    (comp (ref "R105")
      (value "100k")
      (footprint "eagle-import:R0603")
      (libsource (lib "eagle-import") (part "R-US_R0603"))
    )
    (comp (ref "R106")
      (value "33k")
      (footprint "eagle-import:R0603")
      (libsource (lib "eagle-import") (part "R-US_R0603"))
    )
    (comp (ref "R107")
      (value "33k")
      (footprint "eagle-import:R0603")
      (libsource (lib "eagle-import") (part "R-US_R0603"))
    )
    (comp (ref "R108")
      (value "100")
      (footprint "eagle-import:R0603")
      (libsource (lib "eagle-import") (part "R-US_R0603"))
    )
    (comp (ref "R109")
      (value "120k")
      (footprint "eagle-import:R0603")
      (libsource (lib "eagle-import") (part "R-US_R0603"))
    )
    (comp (ref "R110")
      (value "30k")
      (footprint "eagle-import:R0603")
      (libsource (lib "eagle-import") (part "R-US_R0603"))
    )
    (comp (ref "R111")
      (value "50k")
      (footprint "eagle-import:RTRIM3296W")
      (libsource (lib "eagle-import") (part "R-TRIMM3296W"))
    )
    (comp (ref "R112")
      (value "220k")
      (footprint "eagle-import:R0603")
      (libsource (lib "eagle-import") (part "R-US_R0603"))
    )
    (comp (ref "R113")
      (value "3.3M")
      (footprint "eagle-import:R0603")
      (libsource (lib "eagle-import") (part "R-US_R0603"))
    )
    (comp (ref "R114")
      (value "2.49k")
      (footprint "eagle-import:R0805")
      (libsource (lib "eagle-import") (part "R-US_R0805"))
    )
    (comp (ref "C60")
      (value "470n")
      (footprint "eagle-import:C0603")
      (libsource (lib "eagle-import") (part "C-USC0603"))
    )
    (comp (ref "C61")
      (value "47u")
      (footprint "eagle-import:PANASONIC_D")
      (libsource (lib "eagle-import") (part "CPOL-USD"))
    )
    (comp (ref "C62")
      (value "47u")
      (footprint "eagle-import:PANASONIC_D")
      (libsource (lib "eagle-import") (part "CPOL-USD"))
    )
    (comp (ref "C63")
      (value "22u")
      (footprint "eagle-import:PANASONIC_C")
      (libsource (lib "eagle-import") (part "CPOL-USC"))
    )
    (comp (ref "C64")
      (value "100n")
      (footprint "eagle-import:C0603")
      (libsource (lib "eagle-import") (part "C-USC0603"))
    )
    (comp (ref "C65")
      (value "22u")
      (footprint "eagle-import:PANASONIC_C")
      (libsource (lib "eagle-import") (part "CPOL-USC"))
    )
    (comp (ref "C66")
      (value "22u")
      (footprint "eagle-import:PANASONIC_C")
      (libsource (lib "eagle-import") (part "CPOL-USC"))
    )
    (comp (ref "C67")
      (value "100n")
      (footprint "eagle-import:C0603")
      (libsource (lib "eagle-import") (part "C-USC0603"))
    )
    (comp (ref "C68")
      (value "470n")
      (footprint "eagle-import:C0603")
      (libsource (lib "eagle-import") (part "C-USC0603"))
    )
    (comp (ref "D3")
      (value "1N5819HW")
      (footprint "eagle-import:SOD123")
      (libsource (lib "eagle-import") (part "DIODE-SOD123"))
    )
    (comp (ref "D4")
      (value "1N5819HW")
      (footprint "eagle-import:SOD123")
      (libsource (lib "eagle-import") (part "DIODE-SOD123"))
    )
    (comp (ref "IC15")
      (value "LM4040B10")
      (footprint "eagle-import:DBZ_R-PDSO-G3")
      (libsource (lib "eagle-import") (part "LM4041DBZB12"))
    )
    (comp (ref "IC16")
      (value "LM1117-3.3")
      (footprint "eagle-import:SOT223")
      (libsource (lib "eagle-import") (part "REG1117"))
    )
    (comp (ref "IC17")
      (value "LM1117-3.3")
      (footprint "eagle-import:SOT223")
      (libsource (lib "eagle-import") (part "REG1117"))
    )
    (comp (ref "IC18")
      (value "LM4040B25")
      (footprint "eagle-import:DBZ_R-PDSO-G3")
      (libsource (lib "eagle-import") (part "LM4041DBZB12"))
    )
    (comp (ref "POWER1")
      (value "M05X2PTH")
      (footprint "eagle-import:AVR_ICSP")
      (libsource (lib "eagle-import") (part "M05X2PTH"))
    )
    (comp (ref "R115")
      (value "270")
      (footprint "eagle-import:R0603")
      (libsource (lib "eagle-import") (part "R-US_R0603"))
    )
    (comp (ref "R116")
      (value "3.3k")
      (footprint "eagle-import:R0603")
      (libsource (lib "eagle-import") (part "R-US_R0603"))
    )
    (comp (ref "C18")
      (value "100n")
      (footprint "eagle-import:C0603")
      (libsource (lib "eagle-import") (part "C-USC0603"))
    )
    (comp (ref "C19")
      (value "220p")
      (footprint "eagle-import:C0603")
      (libsource (lib "eagle-import") (part "C-USC0603"))
    )
    (comp (ref "C20")
      (value "100n")
      (footprint "eagle-import:C0603")
      (libsource (lib "eagle-import") (part "C-USC0603"))
    )
    (comp (ref "C21")
      (value "220p")
      (footprint "eagle-import:C0603")
      (libsource (lib "eagle-import") (part "C-USC0603"))
    )
    (comp (ref "C22")
      (value "220p")
      (footprint "eagle-import:C0603")
      (libsource (lib "eagle-import") (part "C-USC0603"))
    )
    (comp (ref "C23")
      (value "220p")
      (footprint "eagle-import:C0603")
      (libsource (lib "eagle-import") (part "C-USC0603"))
    )
    (comp (ref "C24")
      (value "100n")
      (footprint "eagle-import:C0603")
      (libsource (lib "eagle-import") (part "C-USC0603"))
    )
    (comp (ref "C25")
      (value "100n")
      (footprint "eagle-import:C0603")
      (libsource (lib "eagle-import") (part "C-USC0603"))
    )
    (comp (ref "C27")
      (value "1n")
      (footprint "eagle-import:C0603")
      (libsource (lib "eagle-import") (part "C-USC0603"))
    )
    (comp (ref "C28")
      (value "10n")
      (footprint "eagle-import:C0603")
      (libsource (lib "eagle-import") (part "C-USC0603"))
    )
    (comp (ref "C29")
      (value "10n")
      (footprint "eagle-import:C0603")
      (libsource (lib "eagle-import") (part "C-USC0603"))
    )
    (comp (ref "C30")
      (value "100n")
      (footprint "eagle-import:C0603")
      (libsource (lib "eagle-import") (part "C-USC0603"))
    )
    (comp (ref "C31")
      (value "1n")
      (footprint "eagle-import:C0603")
      (libsource (lib "eagle-import") (part "C-USC0603"))
    )
    (comp (ref "C32")
      (value "10n")
      (footprint "eagle-import:C0603")
      (libsource (lib "eagle-import") (part "C-USC0603"))
    )
    (comp (ref "C33")
      (value "100n")
      (footprint "eagle-import:C0603")
      (libsource (lib "eagle-import") (part "C-USC0603"))
    )
    (comp (ref "C34")
      (value "1n")
      (footprint "eagle-import:C0603")
      (libsource (lib "eagle-import") (part "C-USC0603"))
    )
    (comp (ref "FM-A")
      (value "SUBMINI_SPDT")
      (footprint "eagle-import:SUBMINI_TOGGLE")
      (libsource (lib "eagle-import") (part "SUBMINI_SPDT"))
    )
    (comp (ref "IC5")
      (value "TL072")
      (footprint "eagle-import:TSSOP-8")
      (libsource (lib "eagle-import") (part "MusicThingModular_TL072TSSOP"))
    )
    (comp (ref "IC6")
      (value "TL072")
      (footprint "eagle-import:TSSOP-8")
      (libsource (lib "eagle-import") (part "MusicThingModular_TL072TSSOP"))
    )
    (comp (ref "IC8")
      (value "MCP6002")
      (footprint "eagle-import:SO08")
      (libsource (lib "eagle-import") (part "TL072D"))
    )
    (comp (ref "IC9")
      (value "MCP6004")
      (footprint "eagle-import:TSSOP14")
      (libsource (lib "eagle-import") (part "MCP6004ST"))
    )
    (comp (ref "J1")
      (value "PJ301_GUI6")
      (footprint "eagle-import:OG-PJ301_VARIATIONS_WQP_PJ_301M6")
      (libsource (lib "eagle-import") (part "PJ301_GUI6"))
    )
    (comp (ref "J2")
      (value "PJ301_GUI6")
      (footprint "eagle-import:OG-PJ301_VARIATIONS_WQP_PJ_301M6")
      (libsource (lib "eagle-import") (part "PJ301_GUI6"))
    )
    (comp (ref "J3")
      (value "PJ301_GUI6")
      (footprint "eagle-import:OG-PJ301_VARIATIONS_WQP_PJ_301M6")
      (libsource (lib "eagle-import") (part "PJ301_GUI6"))
    )
    (comp (ref "J6")
      (value "PJ301_GUI6")
      (footprint "eagle-import:OG-PJ301_VARIATIONS_WQP_PJ_301M6")
      (libsource (lib "eagle-import") (part "PJ301_GUI6"))
    )
    (comp (ref "J7")
      (value "PJ301_GUI6")
      (footprint "eagle-import:OG-PJ301_VARIATIONS_WQP_PJ_301M6")
      (libsource (lib "eagle-import") (part "PJ301_GUI6"))
    )
    (comp (ref "J8")
      (value "PJ301_GUI6")
      (footprint "eagle-import:OG-PJ301_VARIATIONS_WQP_PJ_301M6")
      (libsource (lib "eagle-import") (part "PJ301_GUI6"))
    )
    (comp (ref "J12")
      (value "PJ301_GUI6")
      (footprint "eagle-import:OG-PJ301_VARIATIONS_WQP_PJ_301M6")
      (libsource (lib "eagle-import") (part "PJ301_GUI6"))
    )
    (comp (ref "J13")
      (value "PJ301_GUI6")
      (footprint "eagle-import:OG-PJ301_VARIATIONS_WQP_PJ_301M6")
      (libsource (lib "eagle-import") (part "PJ301_GUI6"))
    )
    (comp (ref "J30")
      (value "PJ301_GUI6")
      (footprint "eagle-import:OG-PJ301_VARIATIONS_WQP_PJ_301M6")
      (libsource (lib "eagle-import") (part "PJ301_GUI6"))
    )
    (comp (ref "MAX")
      (value "PJ301_GUI6")
      (footprint "eagle-import:OG-PJ301_VARIATIONS_WQP_PJ_301M6")
      (libsource (lib "eagle-import") (part "PJ301_GUI6"))
    )
    (comp (ref "MIN")
      (value "PJ301_GUI6")
      (footprint "eagle-import:OG-PJ301_VARIATIONS_WQP_PJ_301M6")
      (libsource (lib "eagle-import") (part "PJ301_GUI6"))
    )
    (comp (ref "MIX")
      (value "PJ301_GUI6")
      (footprint "eagle-import:OG-PJ301_VARIATIONS_WQP_PJ_301M6")
      (libsource (lib "eagle-import") (part "PJ301_GUI6"))
    )
    (comp (ref "R5")
      (value "10kB")
      (footprint "eagle-import:ALPS_POT_VERTICAL_PS")
      (libsource (lib "eagle-import") (part "POT_USVERTICAL_PS"))
    )
    (comp (ref "R6")
      (value "10k")
      (footprint "eagle-import:TALLTRIMMER")
      (libsource (lib "eagle-import") (part "POT-ALPS_POT_US"))
    )
    (comp (ref "R8")
      (value "2.49k")
      (footprint "eagle-import:R0603")
      (libsource (lib "eagle-import") (part "R-US_R0603"))
    )
    (comp (ref "R13")
      (value "33k")
      (footprint "eagle-import:R0603")
      (libsource (lib "eagle-import") (part "R-US_R0603"))
    )
    (comp (ref "R14")
      (value "100k")
      (footprint "eagle-import:R0603")
      (libsource (lib "eagle-import") (part "R-US_R0603"))
    )
    (comp (ref "R15")
      (value "33k")
      (footprint "eagle-import:R0603")
      (libsource (lib "eagle-import") (part "R-US_R0603"))
    )
    (comp (ref "R16")
      (value "100k")
      (footprint "eagle-import:R0603")
      (libsource (lib "eagle-import") (part "R-US_R0603"))
    )
    (comp (ref "R17")
      (value "10kB")
      (footprint "eagle-import:TALLTRIMMER")
      (libsource (lib "eagle-import") (part "POT-ALPS_POT_US"))
    )
    (comp (ref "R18")
      (value "10kB")
      (footprint "eagle-import:TALLTRIMMER")
      (libsource (lib "eagle-import") (part "POT-ALPS_POT_US"))
    )
    (comp (ref "R19")
      (value "10kB")
      (footprint "eagle-import:TALLTRIMMER")
      (libsource (lib "eagle-import") (part "POT-ALPS_POT_US"))
    )
    (comp (ref "R20")
      (value "30k")
      (footprint "eagle-import:R0603")
      (libsource (lib "eagle-import") (part "R-US_R0603"))
    )
    (comp (ref "R21")
      (value "220k")
      (footprint "eagle-import:R0603")
      (libsource (lib "eagle-import") (part "R-US_R0603"))
    )
    (comp (ref "R22")
      (value "100")
      (footprint "eagle-import:R0603")
      (libsource (lib "eagle-import") (part "R-US_R0603"))
    )
    (comp (ref "R23")
      (value "120k")
      (footprint "eagle-import:R0603")
      (libsource (lib "eagle-import") (part "R-US_R0603"))
    )
    (comp (ref "R24")
      (value "100")
      (footprint "eagle-import:R0603")
      (libsource (lib "eagle-import") (part "R-US_R0603"))
    )
    (comp (ref "R25")
      (value "220k")
      (footprint "eagle-import:R0603")
      (libsource (lib "eagle-import") (part "R-US_R0603"))
    )
    (comp (ref "R26")
      (value "100k")
      (footprint "eagle-import:R0603")
      (libsource (lib "eagle-import") (part "R-US_R0603"))
    )
    (comp (ref "R28")
      (value "33k")
      (footprint "eagle-import:R0603")
      (libsource (lib "eagle-import") (part "R-US_R0603"))
    )
    (comp (ref "R29")
      (value "100k")
      (footprint "eagle-import:R0603")
      (libsource (lib "eagle-import") (part "R-US_R0603"))
    )
    (comp (ref "R30")
      (value "100k")
      (footprint "eagle-import:R0603")
      (libsource (lib "eagle-import") (part "R-US_R0603"))
    )
    (comp (ref "R31")
      (value "100k")
      (footprint "eagle-import:R0603")
      (libsource (lib "eagle-import") (part "R-US_R0603"))
    )
    (comp (ref "R32")
      (value "100k")
      (footprint "eagle-import:R0603")
      (libsource (lib "eagle-import") (part "R-US_R0603"))
    )
    (comp (ref "R33")
      (value "33k")
      (footprint "eagle-import:R0603")
      (libsource (lib "eagle-import") (part "R-US_R0603"))
    )
    (comp (ref "R34")
      (value "20k")
      (footprint "eagle-import:R0603")
      (libsource (lib "eagle-import") (part "R-US_R0603"))
    )
    (comp (ref "R35")
      (value "120k")
      (footprint "eagle-import:R0603")
      (libsource (lib "eagle-import") (part "R-US_R0603"))
    )
    (comp (ref "R36")
      (value "100k")
      (footprint "eagle-import:R0603")
      (libsource (lib "eagle-import") (part "R-US_R0603"))
    )
    (comp (ref "R37")
      (value "27k")
      (footprint "eagle-import:R0603")
      (libsource (lib "eagle-import") (part "R-US_R0603"))
    )
    (comp (ref "R38")
      (value "100k")
      (footprint "eagle-import:R0603")
      (libsource (lib "eagle-import") (part "R-US_R0603"))
    )
    (comp (ref "R39")
      (value "100k")
      (footprint "eagle-import:R0603")
      (libsource (lib "eagle-import") (part "R-US_R0603"))
    )
    (comp (ref "R40")
      (value "33k")
      (footprint "eagle-import:R0603")
      (libsource (lib "eagle-import") (part "R-US_R0603"))
    )
    (comp (ref "R41")
      (value "100k")
      (footprint "eagle-import:R0603")
      (libsource (lib "eagle-import") (part "R-US_R0603"))
    )
    (comp (ref "R42")
      (value "100k")
      (footprint "eagle-import:R0603")
      (libsource (lib "eagle-import") (part "R-US_R0603"))
    )
    (comp (ref "R43")
      (value "120k")
      (footprint "eagle-import:R0603")
      (libsource (lib "eagle-import") (part "R-US_R0603"))
    )
    (comp (ref "R44")
      (value "100k")
      (footprint "eagle-import:R0603")
      (libsource (lib "eagle-import") (part "R-US_R0603"))
    )
    (comp (ref "R45")
      (value "39k")
      (footprint "eagle-import:R0603")
      (libsource (lib "eagle-import") (part "R-US_R0603"))
    )
    (comp (ref "R46")
      (value "3.3M")
      (footprint "eagle-import:R0603")
      (libsource (lib "eagle-import") (part "R-US_R0603"))
    )
    (comp (ref "R59")
      (value "50k")
      (footprint "eagle-import:RTRIM3296W")
      (libsource (lib "eagle-import") (part "R-TRIMM3296W"))
    )
    (comp (ref "R60")
      (value "2.49k")
      (footprint "eagle-import:R0805")
      (libsource (lib "eagle-import") (part "R-US_R0805"))
    )
    (comp (ref "R117")
      (value "100kB")
      (footprint "eagle-import:ALPS_POT_VERTICAL_PS")
      (libsource (lib "eagle-import") (part "POT_USVERTICAL_PS"))
    )
    (comp (ref "SYNC-A")
      (value "TL49PO")
      (footprint "eagle-import:TL4XPO")
      (libsource (lib "eagle-import") (part "TL49PO"))
    )
    (comp (ref "SYNC-B")
      (value "SUBMINI_SPDT")
      (footprint "eagle-import:SUBMINI_TOGGLE")
      (libsource (lib "eagle-import") (part "SUBMINI_SPDT"))
    )
    (comp (ref "UNI-BI")
      (value "TL49PO")
      (footprint "eagle-import:TL4XPO")
      (libsource (lib "eagle-import") (part "TL49PO"))
    )
    (comp (ref "C3")
      (value "100n")
      (footprint "eagle-import:C0603")
      (libsource (lib "eagle-import") (part "C-USC0603"))
    )
    (comp (ref "C10")
      (value "100n")
      (footprint "eagle-import:C0603")
      (libsource (lib "eagle-import") (part "C-USC0603"))
    )
    (comp (ref "D5")
      (value "1N4148")
      (footprint "eagle-import:SOD123")
      (libsource (lib "eagle-import") (part "DIODE-SOD123"))
    )
    (comp (ref "D6")
      (value "1N4148")
      (footprint "eagle-import:SOD123")
      (libsource (lib "eagle-import") (part "DIODE-SOD123"))
    )
    (comp (ref "D7")
      (value "1N4148")
      (footprint "eagle-import:SOD123")
      (libsource (lib "eagle-import") (part "DIODE-SOD123"))
    )
    (comp (ref "D8")
      (value "1N4148")
      (footprint "eagle-import:SOD123")
      (libsource (lib "eagle-import") (part "DIODE-SOD123"))
    )
    (comp (ref "D9")
      (value "1N4148")
      (footprint "eagle-import:SOD123")
      (libsource (lib "eagle-import") (part "DIODE-SOD123"))
    )
    (comp (ref "D10")
      (value "1N4148")
      (footprint "eagle-import:SOD123")
      (libsource (lib "eagle-import") (part "DIODE-SOD123"))
    )
    (comp (ref "R118")
      (value "220k")
      (footprint "eagle-import:R0603")
      (libsource (lib "eagle-import") (part "R-US_R0603"))
    )
    (comp (ref "R119")
      (value "180")
      (footprint "eagle-import:R0603")
      (libsource (lib "eagle-import") (part "R-US_R0603"))
    )
    (comp (ref "R120")
      (value "220k")
      (footprint "eagle-import:R0603")
      (libsource (lib "eagle-import") (part "R-US_R0603"))
    )
    (comp (ref "R121")
      (value "180")
      (footprint "eagle-import:R0603")
      (libsource (lib "eagle-import") (part "R-US_R0603"))
    )
    (comp (ref "R122")
      (value "220k")
      (footprint "eagle-import:R0603")
      (libsource (lib "eagle-import") (part "R-US_R0603"))
    )
    (comp (ref "R123")
      (value "220k")
      (footprint "eagle-import:R0603")
      (libsource (lib "eagle-import") (part "R-US_R0603"))
    )
    (comp (ref "U1")
      (value "TL072TSSOP")
      (footprint "eagle-import:TSSOP-8")
      (libsource (lib "eagle-import") (part "TL072TSSOP"))
    )
    (comp (ref "C2")
      (value "18p")
      (footprint "eagle-import:C0603")
      (libsource (lib "eagle-import") (part "C-USC0603"))
    )
    (comp (ref "C4")
      (value "100n")
      (footprint "eagle-import:C0603")
      (libsource (lib "eagle-import") (part "C-USC0603"))
    )
    (comp (ref "C7")
      (value "100n")
      (footprint "eagle-import:C0603")
      (libsource (lib "eagle-import") (part "C-USC0603"))
    )
    (comp (ref "C11")
      (value "3.3u")
      (footprint "eagle-import:C0603")
      (libsource (lib "eagle-import") (part "C-USC0603"))
    )
    (comp (ref "C12")
      (value "100n")
      (footprint "eagle-import:C0603")
      (libsource (lib "eagle-import") (part "C-USC0603"))
    )
    (comp (ref "C14")
      (value "100n")
      (footprint "eagle-import:C0603")
      (libsource (lib "eagle-import") (part "C-USC0603"))
    )
    (comp (ref "C15")
      (value "3.3u")
      (footprint "eagle-import:C0603")
      (libsource (lib "eagle-import") (part "C-USC0603"))
    )
    (comp (ref "C16")
      (value "100n")
      (footprint "eagle-import:C0603")
      (libsource (lib "eagle-import") (part "C-USC0603"))
    )
    (comp (ref "C17")
      (value "18p")
      (footprint "eagle-import:C0603")
      (libsource (lib "eagle-import") (part "C-USC0603"))
    )
    (comp (ref "IC4")
      (value "DAC8552")
      (footprint "eagle-import:MSOP-8")
      (libsource (lib "eagle-import") (part "DAC8552"))
    )
    (comp (ref "J4")
      (value "PJ301_GUI6")
      (footprint "eagle-import:OG-PJ301_VARIATIONS_WQP_PJ_301M6")
      (libsource (lib "eagle-import") (part "PJ301_GUI6"))
    )
    (comp (ref "J5")
      (value "PJ301_GUI6")
      (footprint "eagle-import:OG-PJ301_VARIATIONS_WQP_PJ_301M6")
      (libsource (lib "eagle-import") (part "PJ301_GUI6"))
    )
    (comp (ref "J9")
      (value "PJ301_GUI6")
      (footprint "eagle-import:OG-PJ301_VARIATIONS_WQP_PJ_301M6")
      (libsource (lib "eagle-import") (part "PJ301_GUI6"))
    )
    (comp (ref "J10")
      (value "PJ301_GUI6")
      (footprint "eagle-import:OG-PJ301_VARIATIONS_WQP_PJ_301M6")
      (libsource (lib "eagle-import") (part "PJ301_GUI6"))
    )
    (comp (ref "J11")
      (value "PJ301_GUI6")
      (footprint "eagle-import:OG-PJ301_VARIATIONS_WQP_PJ_301M6")
      (libsource (lib "eagle-import") (part "PJ301_GUI6"))
    )
    (comp (ref "JTAG")
      (value "M05X2MINIJTAG")
      (footprint "eagle-import:2X5-1.27")
      (libsource (lib "eagle-import") (part "M05X2MINIJTAG"))
    )
    (comp (ref "LED1")
      (value "WP115VEGW")
      (footprint "eagle-import:LED-BICOLOR-THROUGHHOLE")
      (libsource (lib "eagle-import") (part "LED-BICOLOR-THROUGHHOLE"))
    )
    (comp (ref "LED2")
      (value "WP115VEGW")
      (footprint "eagle-import:LED-BICOLOR-THROUGHHOLE")
      (libsource (lib "eagle-import") (part "LED-BICOLOR-THROUGHHOLE"))
    )
    (comp (ref "LED3")
      (value "WP115VEGW")
      (footprint "eagle-import:LED-BICOLOR-THROUGHHOLE")
      (libsource (lib "eagle-import") (part "LED-BICOLOR-THROUGHHOLE"))
    )
    (comp (ref "Q1")
      (value "8MHz")
      (footprint "eagle-import:HC49UP")
      (libsource (lib "eagle-import") (part "CRYSTAL-8MHZSMD-HC49UP"))
    )
    (comp (ref "Q2")
      (value "MMBT3904")
      (footprint "eagle-import:SOT23-BEC")
      (libsource (lib "eagle-import") (part "-NPN-SOT23-BECMMBT3904LT1"))
    )
    (comp (ref "Q3")
      (value "MMBT3904")
      (footprint "eagle-import:SOT23-BEC")
      (libsource (lib "eagle-import") (part "-NPN-SOT23-BECMMBT3904LT1"))
    )
    (comp (ref "Q4")
      (value "MMBT3904")
      (footprint "eagle-import:SOT23-BEC")
      (libsource (lib "eagle-import") (part "-NPN-SOT23-BECMMBT3904LT1"))
    )
    (comp (ref "Q5")
      (value "MMBT3904")
      (footprint "eagle-import:SOT23-BEC")
      (libsource (lib "eagle-import") (part "-NPN-SOT23-BECMMBT3904LT1"))
    )
    (comp (ref "Q6")
      (value "MMBT3904")
      (footprint "eagle-import:SOT23-BEC")
      (libsource (lib "eagle-import") (part "-NPN-SOT23-BECMMBT3904LT1"))
    )
    (comp (ref "R2")
      (value "100")
      (footprint "eagle-import:R0603")
      (libsource (lib "eagle-import") (part "R-US_R0603"))
    )
    (comp (ref "R3")
      (value "100")
      (footprint "eagle-import:R0603")
      (libsource (lib "eagle-import") (part "R-US_R0603"))
    )
    (comp (ref "R4")
      (value "100")
      (footprint "eagle-import:R0603")
      (libsource (lib "eagle-import") (part "R-US_R0603"))
    )
    (comp (ref "R7")
      (value "100")
      (footprint "eagle-import:R0603")
      (libsource (lib "eagle-import") (part "R-US_R0603"))
    )
    (comp (ref "R9")
      (value "100")
      (footprint "eagle-import:R0603")
      (libsource (lib "eagle-import") (part "R-US_R0603"))
    )
    (comp (ref "R10")
      (value "100")
      (footprint "eagle-import:R0603")
      (libsource (lib "eagle-import") (part "R-US_R0603"))
    )
    (comp (ref "R47")
      (value "10k")
      (footprint "eagle-import:R0603")
      (libsource (lib "eagle-import") (part "R-US_R0603"))
    )
    (comp (ref "R48")
      (value "10k")
      (footprint "eagle-import:R0603")
      (libsource (lib "eagle-import") (part "R-US_R0603"))
    )
    (comp (ref "R49")
      (value "10k")
      (footprint "eagle-import:R0603")
      (libsource (lib "eagle-import") (part "R-US_R0603"))
    )
    (comp (ref "R50")
      (value "3.3k")
      (footprint "eagle-import:R0603")
      (libsource (lib "eagle-import") (part "R-US_R0603"))
    )
    (comp (ref "R51")
      (value "4.7k")
      (footprint "eagle-import:R0603")
      (libsource (lib "eagle-import") (part "R-US_R0603"))
    )
    (comp (ref "R52")
      (value "3.3k")
      (footprint "eagle-import:R0603")
      (libsource (lib "eagle-import") (part "R-US_R0603"))
    )
    (comp (ref "R53")
      (value "4.7k")
      (footprint "eagle-import:R0603")
      (libsource (lib "eagle-import") (part "R-US_R0603"))
    )
    (comp (ref "R54")
      (value "100k")
      (footprint "eagle-import:R0603")
      (libsource (lib "eagle-import") (part "R-US_R0603"))
    )
    (comp (ref "R55")
      (value "100k")
      (footprint "eagle-import:R0603")
      (libsource (lib "eagle-import") (part "R-US_R0603"))
    )
    (comp (ref "R56")
      (value "100k")
      (footprint "eagle-import:R0603")
      (libsource (lib "eagle-import") (part "R-US_R0603"))
    )
    (comp (ref "R57")
      (value "10k")
      (footprint "eagle-import:R0603")
      (libsource (lib "eagle-import") (part "R-US_R0603"))
    )
    (comp (ref "R58")
      (value "10k")
      (footprint "eagle-import:R0603")
      (libsource (lib "eagle-import") (part "R-US_R0603"))
    )
    (comp (ref "SW3")
      (value "TL1100X")
      (footprint "eagle-import:TL1100X")
      (libsource (lib "eagle-import") (part "TL1100X"))
    )
    (comp (ref "SW4")
      (value "TL1100X")
      (footprint "eagle-import:TL1100X")
      (libsource (lib "eagle-import") (part "TL1100X"))
    )
    (comp (ref "UC1")
      (value "STM32F103CBT6")
      (footprint "eagle-import:LQFP48")
      (libsource (lib "eagle-import") (part "STM32F103CB"))
    )
  )
  (nets
    (net (code "1") (name "+3V3") (class "Default")
      (node (ref "C1") (pin "+") (pinfunction "+_+") (pintype "passive"))
      (node (ref "C14") (pin "1") (pinfunction "1_1") (pintype "passive"))
      (node (ref "C37") (pin "1") (pinfunction "1_1") (pintype "passive"))
      (node (ref "C38") (pin "1") (pinfunction "1_1") (pintype "passive"))
      (node (ref "C39") (pin "1") (pinfunction "1_1") (pintype "passive"))
      (node (ref "C4") (pin "1") (pinfunction "1_1") (pintype "passive"))
      (node (ref "C6") (pin "1") (pinfunction "1_1") (pintype "passive"))
      (node (ref "C63") (pin "+") (pinfunction "+_+") (pintype "passive"))
      (node (ref "C64") (pin "1") (pinfunction "1_1") (pintype "passive"))
      (node (ref "C7") (pin "1") (pinfunction "1_1") (pintype "passive"))
      (node (ref "IC1") (pin "2") (pinfunction "VOUT_2") (pintype "output"))
      (node (ref "IC16") (pin "2") (pinfunction "VOUT_2") (pintype "output"))
      (node (ref "JTAG") (pin "1") (pinfunction "1_1") (pintype "passive"))
      (node (ref "JTAG1") (pin "1") (pinfunction "1_1") (pintype "passive"))
      (node (ref "UC1") (pin "1") (pinfunction "VBAT_1") (pintype "power_in"))
      (node (ref "UC1") (pin "24") (pinfunction "VDD_1_24") (pintype "power_in"))
      (node (ref "UC1") (pin "36") (pinfunction "VDD_2_36") (pintype "power_in"))
      (node (ref "UC1") (pin "48") (pinfunction "VDD_3_48") (pintype "power_in"))
      (node (ref "UC2") (pin "1") (pinfunction "VBAT_1") (pintype "power_in"))
      (node (ref "UC2") (pin "24") (pinfunction "VDD_1_24") (pintype "power_in"))
      (node (ref "UC2") (pin "36") (pinfunction "VDD_2_36") (pintype "power_in"))
      (node (ref "UC2") (pin "48") (pinfunction "VDD_3_48") (pintype "power_in"))
    )
    (net (code "2") (name "+3V3_A") (class "Default")
      (node (ref "C11") (pin "1") (pinfunction "1_1") (pintype "passive"))
      (node (ref "C12") (pin "1") (pinfunction "1_1") (pintype "passive"))
      (node (ref "C15") (pin "1") (pinfunction "1_1") (pintype "passive"))
      (node (ref "C16") (pin "1") (pinfunction "1_1") (pintype "passive"))
      (node (ref "C30") (pin "1") (pinfunction "1_1") (pintype "passive"))
      (node (ref "C33") (pin "1") (pinfunction "1_1") (pintype "passive"))
      (node (ref "C40") (pin "1") (pinfunction "1_1") (pintype "passive"))
      (node (ref "C41") (pin "1") (pinfunction "1_1") (pintype "passive"))
      (node (ref "C42") (pin "1") (pinfunction "1_1") (pintype "passive"))
      (node (ref "C43") (pin "1") (pinfunction "1_1") (pintype "passive"))
      (node (ref "C5") (pin "1") (pinfunction "1_1") (pintype "passive"))
      (node (ref "C50") (pin "1") (pinfunction "1_1") (pintype "passive"))
      (node (ref "C51") (pin "1") (pinfunction "1_1") (pintype "passive"))
      (node (ref "C66") (pin "+") (pinfunction "+_+") (pintype "passive"))
      (node (ref "C67") (pin "1") (pinfunction "1_1") (pintype "passive"))
      (node (ref "C9") (pin "+") (pinfunction "+_+") (pintype "passive"))
      (node (ref "IC10") (pin "1") (pinfunction "VDD_1") (pintype "power_in"))
      (node (ref "IC11") (pin "4") (pinfunction "V+_4") (pintype "power_in"))
      (node (ref "IC12") (pin "8") (pinfunction "V+_8") (pintype "power_in"))
      (node (ref "IC17") (pin "2") (pinfunction "VOUT_2") (pintype "output"))
      (node (ref "IC3") (pin "2") (pinfunction "VOUT_2") (pintype "output"))
      (node (ref "IC4") (pin "1") (pinfunction "VDD_1") (pintype "power_in"))
      (node (ref "IC8") (pin "8") (pinfunction "V+_8") (pintype "power_in"))
      (node (ref "IC9") (pin "4") (pinfunction "V+_4") (pintype "power_in"))
      (node (ref "R113") (pin "2") (pinfunction "2_2") (pintype "passive"))
      (node (ref "R116") (pin "1") (pinfunction "1_1") (pintype "passive"))
      (node (ref "R12") (pin "1") (pinfunction "1_1") (pintype "passive"))
      (node (ref "R46") (pin "2") (pinfunction "2_2") (pintype "passive"))
      (node (ref "R47") (pin "2") (pinfunction "2_2") (pintype "passive"))
      (node (ref "R48") (pin "2") (pinfunction "2_2") (pintype "passive"))
      (node (ref "R49") (pin "2") (pinfunction "2_2") (pintype "passive"))
      (node (ref "R6") (pin "P$1") (pinfunction "E_P$1") (pintype "passive"))
      (node (ref "R72") (pin "2") (pinfunction "2_2") (pintype "passive"))
      (node (ref "R74") (pin "2") (pinfunction "2_2") (pintype "passive"))
      (node (ref "R76") (pin "2") (pinfunction "2_2") (pintype "passive"))
      (node (ref "R79") (pin "P$1") (pinfunction "E_P$1") (pintype "passive"))
      (node (ref "UC1") (pin "9") (pinfunction "VDD_A_9") (pintype "power_in"))
      (node (ref "UC2") (pin "9") (pinfunction "VDD_A_9") (pintype "power_in"))
    )
    (net (code "3") (name "AREF_-10") (class "Default")
      (node (ref "C26") (pin "1") (pinfunction "1_1") (pintype "passive"))
      (node (ref "C60") (pin "1") (pinfunction "1_1") (pintype "passive"))
      (node (ref "IC15") (pin "2") (pinfunction "A_2") (pintype "passive"))
      (node (ref "IC7") (pin "2") (pinfunction "A_2") (pintype "passive"))
      (node (ref "R100") (pin "2") (pinfunction "2_2") (pintype "passive"))
      (node (ref "R111") (pin "2") (pinfunction "S_2") (pintype "passive"))
      (node (ref "R111") (pin "3") (pinfunction "E_3") (pintype "passive"))
      (node (ref "R115") (pin "2") (pinfunction "2_2") (pintype "passive"))
      (node (ref "R17") (pin "P$3") (pinfunction "A_P$3") (pintype "passive"))
      (node (ref "R18") (pin "P$3") (pinfunction "A_P$3") (pintype "passive"))
      (node (ref "R19") (pin "P$3") (pinfunction "A_P$3") (pintype "passive"))
      (node (ref "R27") (pin "2") (pinfunction "2_2") (pintype "passive"))
      (node (ref "R35") (pin "2") (pinfunction "2_2") (pintype "passive"))
      (node (ref "R43") (pin "2") (pinfunction "2_2") (pintype "passive"))
      (node (ref "R5") (pin "P$3") (pinfunction "A_P$3") (pintype "passive"))
      (node (ref "R59") (pin "2") (pinfunction "S_2") (pintype "passive"))
      (node (ref "R59") (pin "3") (pinfunction "E_3") (pintype "passive"))
      (node (ref "R77") (pin "P$3") (pinfunction "A_P$3") (pintype "passive"))
      (node (ref "R78") (pin "P$3") (pinfunction "A_P$3") (pintype "passive"))
      (node (ref "R80") (pin "P$3") (pinfunction "A_P$3") (pintype "passive"))
      (node (ref "R81") (pin "P$3") (pinfunction "A_P$3") (pintype "passive"))
      (node (ref "R93") (pin "2") (pinfunction "2_2") (pintype "passive"))
    )
    (net (code "4") (name "AREF_2.5") (class "Default")
      (node (ref "C13") (pin "1") (pinfunction "1_1") (pintype "passive"))
      (node (ref "C68") (pin "1") (pinfunction "1_1") (pintype "passive"))
      (node (ref "IC10") (pin "2") (pinfunction "VREF_2") (pintype "power_in"))
      (node (ref "IC18") (pin "1") (pinfunction "C_1") (pintype "passive"))
      (node (ref "IC2") (pin "1") (pinfunction "C_1") (pintype "passive"))
      (node (ref "IC4") (pin "2") (pinfunction "VREF_2") (pintype "power_in"))
      (node (ref "R116") (pin "2") (pinfunction "2_2") (pintype "passive"))
      (node (ref "R12") (pin "2") (pinfunction "2_2") (pintype "passive"))
    )
    (net (code "5") (name "ASYM_ADC") (class "Default")
      (node (ref "C29") (pin "2") (pinfunction "2_2") (pintype "passive"))
      (node (ref "C45") (pin "2") (pinfunction "2_2") (pintype "passive"))
      (node (ref "IC11") (pin "14") (pinfunction "OUT_14") (pintype "output"))
      (node (ref "IC9") (pin "14") (pinfunction "OUT_14") (pintype "output"))
      (node (ref "R28") (pin "1") (pinfunction "1_1") (pintype "passive"))
      (node (ref "R86") (pin "1") (pinfunction "1_1") (pintype "passive"))
      (node (ref "UC1") (pin "18") (pinfunction "PB0/ADC12_IN8/TIM3_CH3_18") (pintype "bidirectional"))
      (node (ref "UC2") (pin "18") (pinfunction "PB0/ADC12_IN8/TIM3_CH3_18") (pintype "bidirectional"))
    )
    (net (code "6") (name "ATTENUVERTER_ADC") (class "Default")
      (node (ref "R6") (pin "P$2") (pinfunction "S_P$2") (pintype "passive"))
      (node (ref "R79") (pin "P$2") (pinfunction "S_P$2") (pintype "passive"))
      (node (ref "UC1") (pin "12") (pinfunction "PA2/USART2_TX/ADC12_IN2/TIM2_CH3_12") (pintype "bidirectional"))
      (node (ref "UC2") (pin "12") (pinfunction "PA2/USART2_TX/ADC12_IN2/TIM2_CH3_12") (pintype "bidirectional"))
    )
    (net (code "7") (name "BI") (class "Default")
      (node (ref "IC10") (pin "3") (pinfunction "OUTB_3") (pintype "input"))
      (node (ref "IC4") (pin "3") (pinfunction "OUTB_3") (pintype "input"))
      (node (ref "R106") (pin "2") (pinfunction "2_2") (pintype "passive"))
      (node (ref "R13") (pin "2") (pinfunction "2_2") (pintype "passive"))
    )
    (net (code "8") (name "BOOT_FLASH") (class "Default")
      (node (ref "UC1") (pin "44") (pinfunction "BOOT0_44") (pintype "input"))
      (node (ref "UC2") (pin "44") (pinfunction "BOOT0_44") (pintype "input"))
    )
    (net (code "9") (name "CLOCK") (class "Default")
      (node (ref "Q12") (pin "C") (pinfunction "C_C") (pintype "passive"))
      (node (ref "Q3") (pin "C") (pinfunction "C_C") (pintype "passive"))
      (node (ref "R48") (pin "1") (pinfunction "1_1") (pintype "passive"))
      (node (ref "R76") (pin "1") (pinfunction "1_1") (pintype "passive"))
      (node (ref "UC1") (pin "21") (pinfunction "PB10/I2C2_SCL/USART3_TX_21") (pintype "input"))
      (node (ref "UC2") (pin "21") (pinfunction "PB10/I2C2_SCL/USART3_TX_21") (pintype "input"))
    )
    (net (code "10") (name "CLOCK_A") (class "Default")
      (node (ref "J9") (pin "P2") (pinfunction "2_P2") (pintype "passive"))
      (node (ref "SYNC-A") (pin "5") (pinfunction "P1_5") (pintype "passive"))
    )
    (net (code "11") (name "CYCLE_SW") (class "Default")
      (node (ref "SW2") (pin "3") (pinfunction "S_3") (pintype "passive"))
      (node (ref "SW2") (pin "4") (pinfunction "S1_4") (pintype "passive"))
      (node (ref "SW3") (pin "3") (pinfunction "S_3") (pintype "passive"))
      (node (ref "SW3") (pin "4") (pinfunction "S1_4") (pintype "passive"))
      (node (ref "UC1") (pin "10") (pinfunction "PA0_WKUP/USART2_CTS/ADC12_IN0/TIM2_CH1_ETR_10") (pintype "bidirectional"))
      (node (ref "UC2") (pin "10") (pinfunction "PA0_WKUP/USART2_CTS/ADC12_IN0/TIM2_CH1_ETR_10") (pintype "bidirectional"))
    )
    (net (code "12") (name "DAC_MOSI") (class "Default")
      (node (ref "IC10") (pin "7") (pinfunction "DIN_7") (pintype "bidirectional"))
      (node (ref "IC4") (pin "7") (pinfunction "DIN_7") (pintype "bidirectional"))
      (node (ref "UC1") (pin "28") (pinfunction "PB15/SPI2_MOSI/TIM1_CH3N_28") (pintype "input"))
      (node (ref "UC2") (pin "28") (pinfunction "PB15/SPI2_MOSI/TIM1_CH3N_28") (pintype "input"))
    )
    (net (code "13") (name "DAC_SCK") (class "Default")
      (node (ref "IC10") (pin "6") (pinfunction "SCLK_6") (pintype "bidirectional"))
      (node (ref "IC4") (pin "6") (pinfunction "SCLK_6") (pintype "bidirectional"))
      (node (ref "UC1") (pin "26") (pinfunction "PB13/SPI2_SCK/USART3_CTS/TIM1_CH1N_26") (pintype "input"))
      (node (ref "UC2") (pin "26") (pinfunction "PB13/SPI2_SCK/USART3_CTS/TIM1_CH1N_26") (pintype "input"))
    )
    (net (code "14") (name "DAC_SS") (class "Default")
      (node (ref "IC10") (pin "5") (pinfunction "~{SYNC}_5") (pintype "bidirectional"))
      (node (ref "IC4") (pin "5") (pinfunction "~{SYNC}_5") (pintype "bidirectional"))
      (node (ref "UC1") (pin "25") (pinfunction "PB12/SPI2_NSS/I2C2_SMBA/USART3_CK/TIM1_BKIN_25") (pintype "input"))
      (node (ref "UC2") (pin "25") (pinfunction "PB12/SPI2_NSS/I2C2_SMBA/USART3_CK/TIM1_BKIN_25") (pintype "input"))
    )
    (net (code "15") (name "EOA_B") (class "Default")
      (node (ref "J17") (pin "P3") (pinfunction "3_P3") (pintype "passive"))
      (node (ref "Q8") (pin "C") (pinfunction "C_C") (pintype "passive"))
      (node (ref "R11") (pin "1") (pinfunction "1_1") (pintype "passive"))
      (node (ref "R61") (pin "2") (pinfunction "2_2") (pintype "passive"))
    )
    (net (code "16") (name "EOA_OUT") (class "Default")
      (node (ref "R1") (pin "1") (pinfunction "1_1") (pintype "passive"))
      (node (ref "R57") (pin "1") (pinfunction "1_1") (pintype "passive"))
      (node (ref "UC1") (pin "33") (pinfunction "PA12/USART1_RTS/CAN_TX/TIM1_ETR/USBDP_33") (pintype "bidirectional"))
      (node (ref "UC2") (pin "33") (pinfunction "PA12/USART1_RTS/CAN_TX/TIM1_ETR/USBDP_33") (pintype "bidirectional"))
    )
    (net (code "17") (name "EOD_A") (class "Default")
      (node (ref "J11") (pin "P3") (pinfunction "3_P3") (pintype "passive"))
      (node (ref "Q6") (pin "C") (pinfunction "C_C") (pintype "passive"))
      (node (ref "R52") (pin "2") (pinfunction "2_2") (pintype "passive"))
      (node (ref "R53") (pin "1") (pinfunction "1_1") (pintype "passive"))
      (node (ref "SYNC-B") (pin "3") (pinfunction "S_3") (pintype "passive"))
    )
    (net (code "18") (name "EOD_B") (class "Default")
      (node (ref "J18") (pin "P3") (pinfunction "3_P3") (pintype "passive"))
      (node (ref "Q9") (pin "C") (pinfunction "C_C") (pintype "passive"))
      (node (ref "R63") (pin "1") (pinfunction "1_1") (pintype "passive"))
      (node (ref "R64") (pin "2") (pinfunction "2_2") (pintype "passive"))
      (node (ref "SYNC-A") (pin "1") (pinfunction "O_1") (pintype "passive"))
      (node (ref "SYNC-A") (pin "6") (pinfunction "S1_6") (pintype "passive"))
    )
    (net (code "19") (name "EOD_OUT") (class "Default")
      (node (ref "R58") (pin "1") (pinfunction "1_1") (pintype "passive"))
      (node (ref "R62") (pin "1") (pinfunction "1_1") (pintype "passive"))
      (node (ref "UC1") (pin "32") (pinfunction "PA11/USART1_CTS/CAN_RX/TIM1_CH4/USBDM_32") (pintype "bidirectional"))
      (node (ref "UC2") (pin "32") (pinfunction "PA11/USART1_CTS/CAN_RX/TIM1_CH4/USBDM_32") (pintype "bidirectional"))
    )
    (net (code "20") (name "FM_ADC") (class "Default")
      (node (ref "C27") (pin "2") (pinfunction "2_2") (pintype "passive"))
      (node (ref "C49") (pin "2") (pinfunction "2_2") (pintype "passive"))
      (node (ref "IC12") (pin "7") (pinfunction "OUT_7") (pintype "output"))
      (node (ref "IC8") (pin "7") (pinfunction "OUT_7") (pintype "output"))
      (node (ref "R34") (pin "1") (pinfunction "1_1") (pintype "passive"))
      (node (ref "R99") (pin "1") (pinfunction "1_1") (pintype "passive"))
      (node (ref "UC1") (pin "14") (pinfunction "PA4/SPI1_NSS/USART2_CK/ADC12_IN4_14") (pintype "bidirectional"))
      (node (ref "UC2") (pin "14") (pinfunction "PA4/SPI1_NSS/USART2_CK/ADC12_IN4_14") (pintype "bidirectional"))
    )
    (net (code "21") (name "FREEZE") (class "Default")
      (node (ref "Q11") (pin "C") (pinfunction "C_C") (pintype "passive"))
      (node (ref "Q4") (pin "C") (pinfunction "C_C") (pintype "passive"))
      (node (ref "R49") (pin "1") (pinfunction "1_1") (pintype "passive"))
      (node (ref "R74") (pin "1") (pinfunction "1_1") (pintype "passive"))
      (node (ref "UC1") (pin "19") (pinfunction "PB1/ADC12_IN9/TIM3_CH4_19") (pintype "bidirectional"))
      (node (ref "UC2") (pin "19") (pinfunction "PB1/ADC12_IN9/TIM3_CH4_19") (pintype "bidirectional"))
    )
    (net (code "22") (name "GND") (class "Default")
      (node (ref "C1") (pin "-") (pinfunction "-_-") (pintype "passive"))
      (node (ref "C10") (pin "1") (pinfunction "1_1") (pintype "passive"))
      (node (ref "C11") (pin "2") (pinfunction "2_2") (pintype "passive"))
      (node (ref "C12") (pin "2") (pinfunction "2_2") (pintype "passive"))
      (node (ref "C13") (pin "2") (pinfunction "2_2") (pintype "passive"))
      (node (ref "C14") (pin "2") (pinfunction "2_2") (pintype "passive"))
      (node (ref "C15") (pin "2") (pinfunction "2_2") (pintype "passive"))
      (node (ref "C16") (pin "2") (pinfunction "2_2") (pintype "passive"))
      (node (ref "C17") (pin "1") (pinfunction "1_1") (pintype "passive"))
      (node (ref "C18") (pin "2") (pinfunction "2_2") (pintype "passive"))
      (node (ref "C2") (pin "1") (pinfunction "1_1") (pintype "passive"))
      (node (ref "C20") (pin "2") (pinfunction "2_2") (pintype "passive"))
      (node (ref "C22") (pin "2") (pinfunction "2_2") (pintype "passive"))
      (node (ref "C23") (pin "2") (pinfunction "2_2") (pintype "passive"))
      (node (ref "C24") (pin "1") (pinfunction "1_1") (pintype "passive"))
      (node (ref "C25") (pin "1") (pinfunction "1_1") (pintype "passive"))
      (node (ref "C26") (pin "2") (pinfunction "2_2") (pintype "passive"))
      (node (ref "C3") (pin "2") (pinfunction "2_2") (pintype "passive"))
      (node (ref "C30") (pin "2") (pinfunction "2_2") (pintype "passive"))
      (node (ref "C33") (pin "2") (pinfunction "2_2") (pintype "passive"))
      (node (ref "C35") (pin "1") (pinfunction "1_1") (pintype "passive"))
      (node (ref "C36") (pin "1") (pinfunction "1_1") (pintype "passive"))
      (node (ref "C37") (pin "2") (pinfunction "2_2") (pintype "passive"))
      (node (ref "C38") (pin "2") (pinfunction "2_2") (pintype "passive"))
      (node (ref "C39") (pin "2") (pinfunction "2_2") (pintype "passive"))
      (node (ref "C4") (pin "2") (pinfunction "2_2") (pintype "passive"))
      (node (ref "C40") (pin "2") (pinfunction "2_2") (pintype "passive"))
      (node (ref "C41") (pin "2") (pinfunction "2_2") (pintype "passive"))
      (node (ref "C42") (pin "2") (pinfunction "2_2") (pintype "passive"))
      (node (ref "C43") (pin "2") (pinfunction "2_2") (pintype "passive"))
      (node (ref "C5") (pin "2") (pinfunction "2_2") (pintype "passive"))
      (node (ref "C50") (pin "2") (pinfunction "2_2") (pintype "passive"))
      (node (ref "C51") (pin "2") (pinfunction "2_2") (pintype "passive"))
      (node (ref "C52") (pin "2") (pinfunction "2_2") (pintype "passive"))
      (node (ref "C54") (pin "2") (pinfunction "2_2") (pintype "passive"))
      (node (ref "C56") (pin "2") (pinfunction "2_2") (pintype "passive"))
      (node (ref "C57") (pin "2") (pinfunction "2_2") (pintype "passive"))
      (node (ref "C58") (pin "1") (pinfunction "1_1") (pintype "passive"))
      (node (ref "C59") (pin "1") (pinfunction "1_1") (pintype "passive"))
      (node (ref "C6") (pin "2") (pinfunction "2_2") (pintype "passive"))
      (node (ref "C60") (pin "2") (pinfunction "2_2") (pintype "passive"))
      (node (ref "C61") (pin "-") (pinfunction "-_-") (pintype "passive"))
      (node (ref "C62") (pin "+") (pinfunction "+_+") (pintype "passive"))
      (node (ref "C63") (pin "-") (pinfunction "-_-") (pintype "passive"))
      (node (ref "C64") (pin "2") (pinfunction "2_2") (pintype "passive"))
      (node (ref "C65") (pin "-") (pinfunction "-_-") (pintype "passive"))
      (node (ref "C66") (pin "-") (pinfunction "-_-") (pintype "passive"))
      (node (ref "C67") (pin "2") (pinfunction "2_2") (pintype "passive"))
      (node (ref "C68") (pin "2") (pinfunction "2_2") (pintype "passive"))
      (node (ref "C7") (pin "2") (pinfunction "2_2") (pintype "passive"))
      (node (ref "C8") (pin "-") (pinfunction "-_-") (pintype "passive"))
      (node (ref "C9") (pin "-") (pinfunction "-_-") (pintype "passive"))
      (node (ref "IC1") (pin "1") (pinfunction "GND_1") (pintype "power_in"))
      (node (ref "IC10") (pin "8") (pinfunction "GND_8") (pintype "power_in"))
      (node (ref "IC11") (pin "10") (pinfunction "+IN_10") (pintype "input"))
      (node (ref "IC11") (pin "11") (pinfunction "V-_11") (pintype "power_in"))
      (node (ref "IC11") (pin "12") (pinfunction "+IN_12") (pintype "input"))
      (node (ref "IC11") (pin "3") (pinfunction "+IN_3") (pintype "input"))
      (node (ref "IC11") (pin "5") (pinfunction "+IN_5") (pintype "input"))
      (node (ref "IC12") (pin "3") (pinfunction "+IN_3") (pintype "input"))
      (node (ref "IC12") (pin "4") (pinfunction "V-_4") (pintype "power_in"))
      (node (ref "IC12") (pin "5") (pinfunction "+IN_5") (pintype "input"))
      (node (ref "IC14") (pin "3") (pinfunction "+IN_3") (pintype "input"))
      (node (ref "IC15") (pin "1") (pinfunction "C_1") (pintype "passive"))
      (node (ref "IC16") (pin "1") (pinfunction "GND_1") (pintype "power_in"))
      (node (ref "IC17") (pin "1") (pinfunction "GND_1") (pintype "power_in"))
      (node (ref "IC18") (pin "2") (pinfunction "A_2") (pintype "passive"))
      (node (ref "IC2") (pin "2") (pinfunction "A_2") (pintype "passive"))
      (node (ref "IC3") (pin "1") (pinfunction "GND_1") (pintype "power_in"))
      (node (ref "IC4") (pin "8") (pinfunction "GND_8") (pintype "power_in"))
      (node (ref "IC5") (pin "3") (pinfunction "+IN_3") (pintype "input"))
      (node (ref "IC7") (pin "1") (pinfunction "C_1") (pintype "passive"))
      (node (ref "IC8") (pin "3") (pinfunction "+IN_3") (pintype "input"))
      (node (ref "IC8") (pin "4") (pinfunction "V-_4") (pintype "power_in"))
      (node (ref "IC8") (pin "5") (pinfunction "+IN_5") (pintype "input"))
      (node (ref "IC9") (pin "10") (pinfunction "+IN_10") (pintype "input"))
      (node (ref "IC9") (pin "11") (pinfunction "V-_11") (pintype "power_in"))
      (node (ref "IC9") (pin "12") (pinfunction "+IN_12") (pintype "input"))
      (node (ref "IC9") (pin "3") (pinfunction "+IN_3") (pintype "input"))
      (node (ref "IC9") (pin "5") (pinfunction "+IN_5") (pintype "input"))
      (node (ref "J1") (pin "P1") (pinfunction "1_P1") (pintype "passive"))
      (node (ref "J10") (pin "P1") (pinfunction "1_P1") (pintype "passive"))
      (node (ref "J11") (pin "P1") (pinfunction "1_P1") (pintype "passive"))
      (node (ref "J12") (pin "P1") (pinfunction "1_P1") (pintype "passive"))
      (node (ref "J13") (pin "P1") (pinfunction "1_P1") (pintype "passive"))
      (node (ref "J14") (pin "P1") (pinfunction "1_P1") (pintype "passive"))
      (node (ref "J15") (pin "P1") (pinfunction "1_P1") (pintype "passive"))
      (node (ref "J15") (pin "P2") (pinfunction "2_P2") (pintype "passive"))
      (node (ref "J16") (pin "P1") (pinfunction "1_P1") (pintype "passive"))
      (node (ref "J16") (pin "P2") (pinfunction "2_P2") (pintype "passive"))
      (node (ref "J17") (pin "P1") (pinfunction "1_P1") (pintype "passive"))
      (node (ref "J18") (pin "P1") (pinfunction "1_P1") (pintype "passive"))
      (node (ref "J19") (pin "P1") (pinfunction "1_P1") (pintype "passive"))
      (node (ref "J2") (pin "P1") (pinfunction "1_P1") (pintype "passive"))
      (node (ref "J20") (pin "P1") (pinfunction "1_P1") (pintype "passive"))
      (node (ref "J21") (pin "P1") (pinfunction "1_P1") (pintype "passive"))
      (node (ref "J22") (pin "P1") (pinfunction "1_P1") (pintype "passive"))
      (node (ref "J23") (pin "P1") (pinfunction "1_P1") (pintype "passive"))
      (node (ref "J24") (pin "P1") (pinfunction "1_P1") (pintype "passive"))
      (node (ref "J25") (pin "P1") (pinfunction "1_P1") (pintype "passive"))
      (node (ref "J26") (pin "P1") (pinfunction "1_P1") (pintype "passive"))
      (node (ref "J3") (pin "P1") (pinfunction "1_P1") (pintype "passive"))
      (node (ref "J30") (pin "P1") (pinfunction "1_P1") (pintype "passive"))
      (node (ref "J4") (pin "P1") (pinfunction "1_P1") (pintype "passive"))
      (node (ref "J5") (pin "P1") (pinfunction "1_P1") (pintype "passive"))
      (node (ref "J5") (pin "P2") (pinfunction "2_P2") (pintype "passive"))
      (node (ref "J6") (pin "P1") (pinfunction "1_P1") (pintype "passive"))
      (node (ref "J7") (pin "P1") (pinfunction "1_P1") (pintype "passive"))
      (node (ref "J8") (pin "P1") (pinfunction "1_P1") (pintype "passive"))
      (node (ref "J9") (pin "P1") (pinfunction "1_P1") (pintype "passive"))
      (node (ref "JTAG") (pin "3") (pinfunction "3_3") (pintype "passive"))
      (node (ref "JTAG") (pin "5") (pinfunction "5_5") (pintype "passive"))
      (node (ref "JTAG") (pin "9") (pinfunction "9_9") (pintype "passive"))
      (node (ref "JTAG1") (pin "3") (pinfunction "3_3") (pintype "passive"))
      (node (ref "JTAG1") (pin "5") (pinfunction "5_5") (pintype "passive"))
      (node (ref "JTAG1") (pin "9") (pinfunction "9_9") (pintype "passive"))
      (node (ref "LED1") (pin "2") (pinfunction "C_2") (pintype "bidirectional"))
      (node (ref "LED2") (pin "2") (pinfunction "C_2") (pintype "bidirectional"))
      (node (ref "LED3") (pin "2") (pinfunction "C_2") (pintype "bidirectional"))
      (node (ref "LED4") (pin "2") (pinfunction "C_2") (pintype "bidirectional"))
      (node (ref "LED5") (pin "2") (pinfunction "C_2") (pintype "bidirectional"))
      (node (ref "LED6") (pin "2") (pinfunction "C_2") (pintype "bidirectional"))
      (node (ref "MAX") (pin "P1") (pinfunction "1_P1") (pintype "passive"))
      (node (ref "MIN") (pin "P1") (pinfunction "1_P1") (pintype "passive"))
      (node (ref "MIX") (pin "P1") (pinfunction "1_P1") (pintype "passive"))
      (node (ref "POWER1") (pin "3") (pinfunction "3_3") (pintype "passive"))
      (node (ref "POWER1") (pin "4") (pinfunction "4_4") (pintype "passive"))
      (node (ref "POWER1") (pin "5") (pinfunction "5_5") (pintype "passive"))
      (node (ref "POWER1") (pin "6") (pinfunction "6_6") (pintype "passive"))
      (node (ref "POWER1") (pin "7") (pinfunction "7_7") (pintype "passive"))
      (node (ref "POWER1") (pin "8") (pinfunction "8_8") (pintype "passive"))
      (node (ref "Q10") (pin "E") (pinfunction "E_E") (pintype "passive"))
      (node (ref "Q11") (pin "E") (pinfunction "E_E") (pintype "passive"))
      (node (ref "Q12") (pin "E") (pinfunction "E_E") (pintype "passive"))
      (node (ref "Q2") (pin "E") (pinfunction "E_E") (pintype "passive"))
      (node (ref "Q3") (pin "E") (pinfunction "E_E") (pintype "passive"))
      (node (ref "Q4") (pin "E") (pinfunction "E_E") (pintype "passive"))
      (node (ref "Q5") (pin "E") (pinfunction "E_E") (pintype "passive"))
      (node (ref "Q6") (pin "E") (pinfunction "E_E") (pintype "passive"))
      (node (ref "Q8") (pin "E") (pinfunction "E_E") (pintype "passive"))
      (node (ref "Q9") (pin "E") (pinfunction "E_E") (pintype "passive"))
      (node (ref "R105") (pin "1") (pinfunction "1_1") (pintype "passive"))
      (node (ref "R17") (pin "P$1") (pinfunction "E_P$1") (pintype "passive"))
      (node (ref "R18") (pin "P$1") (pinfunction "E_P$1") (pintype "passive"))
      (node (ref "R19") (pin "P$1") (pinfunction "E_P$1") (pintype "passive"))
      (node (ref "R26") (pin "1") (pinfunction "1_1") (pintype "passive"))
      (node (ref "R50") (pin "1") (pinfunction "1_1") (pintype "passive"))
      (node (ref "R52") (pin "1") (pinfunction "1_1") (pintype "passive"))
      (node (ref "R6") (pin "P$3") (pinfunction "A_P$3") (pintype "passive"))
      (node (ref "R61") (pin "1") (pinfunction "1_1") (pintype "passive"))
      (node (ref "R64") (pin "1") (pinfunction "1_1") (pintype "passive"))
      (node (ref "R77") (pin "P$1") (pinfunction "E_P$1") (pintype "passive"))
      (node (ref "R79") (pin "P$3") (pinfunction "A_P$3") (pintype "passive"))
      (node (ref "R8") (pin "1") (pinfunction "1_1") (pintype "passive"))
      (node (ref "R80") (pin "P$1") (pinfunction "E_P$1") (pintype "passive"))
      (node (ref "R81") (pin "P$1") (pinfunction "E_P$1") (pintype "passive"))
      (node (ref "R97") (pin "1") (pinfunction "1_1") (pintype "passive"))
      (node (ref "SW1") (pin "1") (pinfunction "P_1") (pintype "passive"))
      (node (ref "SW1") (pin "2") (pinfunction "P1_2") (pintype "passive"))
      (node (ref "SW2") (pin "1") (pinfunction "P_1") (pintype "passive"))
      (node (ref "SW2") (pin "2") (pinfunction "P1_2") (pintype "passive"))
      (node (ref "SW3") (pin "1") (pinfunction "P_1") (pintype "passive"))
      (node (ref "SW3") (pin "2") (pinfunction "P1_2") (pintype "passive"))
      (node (ref "SW4") (pin "1") (pinfunction "P_1") (pintype "passive"))
      (node (ref "SW4") (pin "2") (pinfunction "P1_2") (pintype "passive"))
      (node (ref "SYNC-A") (pin "3") (pinfunction "S_3") (pintype "passive"))
      (node (ref "SYNC-A") (pin "4") (pinfunction "O1_4") (pintype "passive"))
      (node (ref "SYNC-B") (pin "1") (pinfunction "O_1") (pintype "passive"))
      (node (ref "UC1") (pin "20") (pinfunction "PB2/BOOT1_20") (pintype "bidirectional"))
      (node (ref "UC1") (pin "23") (pinfunction "VSS_1_23") (pintype "power_in"))
      (node (ref "UC1") (pin "35") (pinfunction "VSS_2_35") (pintype "power_in"))
      (node (ref "UC1") (pin "47") (pinfunction "VSS_3_47") (pintype "power_in"))
      (node (ref "UC1") (pin "8") (pinfunction "VSS_A_8") (pintype "power_in"))
      (node (ref "UC2") (pin "20") (pinfunction "PB2/BOOT1_20") (pintype "bidirectional"))
      (node (ref "UC2") (pin "23") (pinfunction "VSS_1_23") (pintype "power_in"))
      (node (ref "UC2") (pin "35") (pinfunction "VSS_2_35") (pintype "power_in"))
      (node (ref "UC2") (pin "47") (pinfunction "VSS_3_47") (pintype "power_in"))
      (node (ref "UC2") (pin "8") (pinfunction "VSS_A_8") (pintype "power_in"))
    )
    (net (code "23") (name "JTCK") (class "Default")
      (node (ref "JTAG") (pin "4") (pinfunction "4_4") (pintype "passive"))
      (node (ref "JTAG1") (pin "4") (pinfunction "4_4") (pintype "passive"))
      (node (ref "UC1") (pin "37") (pinfunction "PA14/JTCK/SWCLK_37") (pintype "bidirectional"))
      (node (ref "UC2") (pin "37") (pinfunction "PA14/JTCK/SWCLK_37") (pintype "bidirectional"))
    )
    (net (code "24") (name "JTDI") (class "Default")
      (node (ref "JTAG") (pin "8") (pinfunction "8_8") (pintype "passive"))
      (node (ref "JTAG1") (pin "8") (pinfunction "8_8") (pintype "passive"))
      (node (ref "UC1") (pin "38") (pinfunction "PA15/JTDI_38") (pintype "bidirectional"))
      (node (ref "UC2") (pin "38") (pinfunction "PA15/JTDI_38") (pintype "bidirectional"))
    )
    (net (code "25") (name "JTDO") (class "Default")
      (node (ref "JTAG") (pin "6") (pinfunction "6_6") (pintype "passive"))
      (node (ref "JTAG1") (pin "6") (pinfunction "6_6") (pintype "passive"))
      (node (ref "UC1") (pin "39") (pinfunction "PB3/JTDO_39") (pintype "bidirectional"))
      (node (ref "UC2") (pin "39") (pinfunction "PB3/JTDO_39") (pintype "bidirectional"))
    )
    (net (code "26") (name "JTMS") (class "Default")
      (node (ref "JTAG") (pin "2") (pinfunction "2_2") (pintype "passive"))
      (node (ref "JTAG1") (pin "2") (pinfunction "2_2") (pintype "passive"))
      (node (ref "UC1") (pin "34") (pinfunction "PA13/JTMS/SWDIO_34") (pintype "bidirectional"))
      (node (ref "UC2") (pin "34") (pinfunction "PA13/JTMS/SWDIO_34") (pintype "bidirectional"))
    )
    (net (code "27") (name "LEVEL_ADC") (class "Default")
      (node (ref "C34") (pin "2") (pinfunction "2_2") (pintype "passive"))
      (node (ref "C47") (pin "2") (pinfunction "2_2") (pintype "passive"))
      (node (ref "IC11") (pin "7") (pinfunction "OUT_7") (pintype "output"))
      (node (ref "IC9") (pin "7") (pinfunction "OUT_7") (pintype "output"))
      (node (ref "R45") (pin "1") (pinfunction "1_1") (pintype "passive"))
      (node (ref "R92") (pin "1") (pinfunction "1_1") (pintype "passive"))
      (node (ref "UC1") (pin "16") (pinfunction "PA6/SPI1_MISO/ADC12_IN6/TIM3_CH1_16") (pintype "bidirectional"))
      (node (ref "UC2") (pin "16") (pinfunction "PA6/SPI1_MISO/ADC12_IN6/TIM3_CH1_16") (pintype "bidirectional"))
    )
    (net (code "28") (name "MAX-OUT") (class "Default")
      (node (ref "MAX") (pin "P3") (pinfunction "3_P3") (pintype "passive"))
      (node (ref "R119") (pin "1") (pinfunction "1_1") (pintype "passive"))
    )
    (net (code "29") (name "MIN-OUT") (class "Default")
      (node (ref "MIN") (pin "P3") (pinfunction "3_P3") (pintype "passive"))
      (node (ref "R121") (pin "1") (pinfunction "1_1") (pintype "passive"))
    )
    (net (code "30") (name "MIXED_OUT") (class "Default")
      (node (ref "MIX") (pin "P3") (pinfunction "3_P3") (pintype "passive"))
      (node (ref "R117") (pin "P$2") (pinfunction "S_P$2") (pintype "passive"))
    )
    (net (code "31") (name "Net-(C19-Pad1)") (class "Default")
      (node (ref "C19") (pin "1") (pinfunction "1_1") (pintype "passive"))
      (node (ref "R13") (pin "1") (pinfunction "1_1") (pintype "passive"))
      (node (ref "R15") (pin "2") (pinfunction "2_2") (pintype "passive"))
    )
    (net (code "32") (name "Net-(C21-Pad1)") (class "Default")
      (node (ref "C21") (pin "1") (pinfunction "1_1") (pintype "passive"))
      (node (ref "R14") (pin "1") (pinfunction "1_1") (pintype "passive"))
      (node (ref "R16") (pin "2") (pinfunction "2_2") (pintype "passive"))
    )
    (net (code "33") (name "Net-(C53-Pad1)") (class "Default")
      (node (ref "C53") (pin "1") (pinfunction "1_1") (pintype "passive"))
      (node (ref "R101") (pin "1") (pinfunction "1_1") (pintype "passive"))
      (node (ref "R102") (pin "2") (pinfunction "2_2") (pintype "passive"))
    )
    (net (code "34") (name "Net-(C55-Pad1)") (class "Default")
      (node (ref "C55") (pin "1") (pinfunction "1_1") (pintype "passive"))
      (node (ref "R106") (pin "1") (pinfunction "1_1") (pintype "passive"))
      (node (ref "R107") (pin "2") (pinfunction "2_2") (pintype "passive"))
    )
    (net (code "35") (name "Net-(D3-PadA)") (class "Default")
      (node (ref "D3") (pin "A") (pinfunction "A_A") (pintype "passive"))
      (node (ref "POWER1") (pin "1") (pinfunction "1_1") (pintype "passive"))
      (node (ref "POWER1") (pin "2") (pinfunction "2_2") (pintype "passive"))
    )
    (net (code "36") (name "Net-(D4-PadC)") (class "Default")
      (node (ref "D4") (pin "C") (pinfunction "C_C") (pintype "passive"))
      (node (ref "POWER1") (pin "10") (pinfunction "10_10") (pintype "passive"))
      (node (ref "POWER1") (pin "9") (pinfunction "9_9") (pintype "passive"))
    )
    (net (code "37") (name "Net-(FM-A-COMMON)") (class "Default")
      (node (ref "FM-A") (pin "COM") (pinfunction "COMMON_COM") (pintype "passive"))
      (node (ref "J7") (pin "P2") (pinfunction "2_P2") (pintype "passive"))
    )
    (net (code "38") (name "Net-(FM-A-S)") (class "Default")
      (node (ref "FM-A") (pin "3") (pinfunction "S_3") (pintype "passive"))
      (node (ref "R46") (pin "1") (pinfunction "1_1") (pintype "passive"))
    )
    (net (code "39") (name "Net-(IC5A--IN)") (class "Default")
      (node (ref "IC5") (pin "2") (pinfunction "-IN_2") (pintype "input"))
      (node (ref "R20") (pin "1") (pinfunction "1_1") (pintype "passive"))
      (node (ref "R21") (pin "1") (pinfunction "1_1") (pintype "passive"))
      (node (ref "R23") (pin "2") (pinfunction "2_2") (pintype "passive"))
    )
    (net (code "40") (name "Net-(IC5A-OUT)") (class "Default")
      (node (ref "IC5") (pin "1") (pinfunction "OUT_1") (pintype "output"))
      (node (ref "R22") (pin "2") (pinfunction "2_2") (pintype "passive"))
      (node (ref "R23") (pin "1") (pinfunction "1_1") (pintype "passive"))
    )
    (net (code "41") (name "Net-(IC5B-+IN)") (class "Default")
      (node (ref "C22") (pin "1") (pinfunction "1_1") (pintype "passive"))
      (node (ref "IC5") (pin "5") (pinfunction "+IN_5") (pintype "input"))
      (node (ref "R15") (pin "1") (pinfunction "1_1") (pintype "passive"))
    )
    (net (code "42") (name "Net-(IC5B--IN)") (class "Default")
      (node (ref "C19") (pin "2") (pinfunction "2_2") (pintype "passive"))
      (node (ref "IC5") (pin "6") (pinfunction "-IN_6") (pintype "input"))
      (node (ref "IC5") (pin "7") (pinfunction "OUT_7") (pintype "output"))
      (node (ref "R20") (pin "2") (pinfunction "2_2") (pintype "passive"))
    )
    (net (code "43") (name "Net-(IC6A-+IN)") (class "Default")
      (node (ref "C21") (pin "2") (pinfunction "2_2") (pintype "passive"))
      (node (ref "IC6") (pin "3") (pinfunction "+IN_3") (pintype "input"))
      (node (ref "IC6") (pin "6") (pinfunction "-IN_6") (pintype "input"))
      (node (ref "IC6") (pin "7") (pinfunction "OUT_7") (pintype "output"))
    )
    (net (code "44") (name "Net-(IC6A--IN)") (class "Default")
      (node (ref "IC6") (pin "2") (pinfunction "-IN_2") (pintype "input"))
      (node (ref "R25") (pin "2") (pinfunction "2_2") (pintype "passive"))
      (node (ref "R26") (pin "2") (pinfunction "2_2") (pintype "passive"))
    )
    (net (code "45") (name "Net-(IC6A-OUT)") (class "Default")
      (node (ref "IC6") (pin "1") (pinfunction "OUT_1") (pintype "output"))
      (node (ref "R24") (pin "2") (pinfunction "2_2") (pintype "passive"))
      (node (ref "R25") (pin "1") (pinfunction "1_1") (pintype "passive"))
    )
    (net (code "46") (name "Net-(IC6B-+IN)") (class "Default")
      (node (ref "C23") (pin "1") (pinfunction "1_1") (pintype "passive"))
      (node (ref "IC6") (pin "5") (pinfunction "+IN_5") (pintype "input"))
      (node (ref "R16") (pin "1") (pinfunction "1_1") (pintype "passive"))
    )
    (net (code "47") (name "Net-(IC8A--IN)") (class "Default")
      (node (ref "C31") (pin "1") (pinfunction "1_1") (pintype "passive"))
      (node (ref "IC8") (pin "2") (pinfunction "-IN_2") (pintype "input"))
      (node (ref "R37") (pin "2") (pinfunction "2_2") (pintype "passive"))
      (node (ref "R38") (pin "1") (pinfunction "1_1") (pintype "passive"))
      (node (ref "R39") (pin "1") (pinfunction "1_1") (pintype "passive"))
    )
    (net (code "48") (name "Net-(IC8B--IN)") (class "Default")
      (node (ref "C27") (pin "1") (pinfunction "1_1") (pintype "passive"))
      (node (ref "IC8") (pin "6") (pinfunction "-IN_6") (pintype "input"))
      (node (ref "R34") (pin "2") (pinfunction "2_2") (pintype "passive"))
      (node (ref "R35") (pin "1") (pinfunction "1_1") (pintype "passive"))
      (node (ref "R36") (pin "1") (pinfunction "1_1") (pintype "passive"))
    )
    (net (code "49") (name "Net-(IC9A--IN)") (class "Default")
      (node (ref "C32") (pin "1") (pinfunction "1_1") (pintype "passive"))
      (node (ref "IC9") (pin "2") (pinfunction "-IN_2") (pintype "input"))
      (node (ref "R40") (pin "2") (pinfunction "2_2") (pintype "passive"))
      (node (ref "R41") (pin "1") (pinfunction "1_1") (pintype "passive"))
      (node (ref "R42") (pin "1") (pinfunction "1_1") (pintype "passive"))
    )
    (net (code "50") (name "Net-(IC9B--IN)") (class "Default")
      (node (ref "C34") (pin "1") (pinfunction "1_1") (pintype "passive"))
      (node (ref "IC9") (pin "6") (pinfunction "-IN_6") (pintype "input"))
      (node (ref "R43") (pin "1") (pinfunction "1_1") (pintype "passive"))
      (node (ref "R44") (pin "1") (pinfunction "1_1") (pintype "passive"))
      (node (ref "R45") (pin "2") (pinfunction "2_2") (pintype "passive"))
    )
    (net (code "51") (name "Net-(IC9C--IN)") (class "Default")
      (node (ref "C28") (pin "1") (pinfunction "1_1") (pintype "passive"))
      (node (ref "IC9") (pin "9") (pinfunction "-IN_9") (pintype "input"))
      (node (ref "R31") (pin "1") (pinfunction "1_1") (pintype "passive"))
      (node (ref "R32") (pin "1") (pinfunction "1_1") (pintype "passive"))
      (node (ref "R33") (pin "2") (pinfunction "2_2") (pintype "passive"))
    )
    (net (code "52") (name "Net-(IC9D--IN)") (class "Default")
      (node (ref "C29") (pin "1") (pinfunction "1_1") (pintype "passive"))
      (node (ref "IC9") (pin "13") (pinfunction "-IN_13") (pintype "input"))
      (node (ref "R28") (pin "2") (pinfunction "2_2") (pintype "passive"))
      (node (ref "R29") (pin "1") (pinfunction "1_1") (pintype "passive"))
      (node (ref "R30") (pin "1") (pinfunction "1_1") (pintype "passive"))
    )
    (net (code "53") (name "Net-(IC11A--IN)") (class "Default")
      (node (ref "C44") (pin "1") (pinfunction "1_1") (pintype "passive"))
      (node (ref "IC11") (pin "2") (pinfunction "-IN_2") (pintype "input"))
      (node (ref "R82") (pin "1") (pinfunction "1_1") (pintype "passive"))
      (node (ref "R83") (pin "2") (pinfunction "2_2") (pintype "passive"))
      (node (ref "R84") (pin "1") (pinfunction "1_1") (pintype "passive"))
    )
    (net (code "54") (name "Net-(IC11B--IN)") (class "Default")
      (node (ref "C47") (pin "1") (pinfunction "1_1") (pintype "passive"))
      (node (ref "IC11") (pin "6") (pinfunction "-IN_6") (pintype "input"))
      (node (ref "R91") (pin "1") (pinfunction "1_1") (pintype "passive"))
      (node (ref "R92") (pin "2") (pinfunction "2_2") (pintype "passive"))
      (node (ref "R93") (pin "1") (pinfunction "1_1") (pintype "passive"))
    )
    (net (code "55") (name "Net-(IC11C--IN)") (class "Default")
      (node (ref "C46") (pin "1") (pinfunction "1_1") (pintype "passive"))
      (node (ref "IC11") (pin "9") (pinfunction "-IN_9") (pintype "input"))
      (node (ref "R88") (pin "1") (pinfunction "1_1") (pintype "passive"))
      (node (ref "R89") (pin "2") (pinfunction "2_2") (pintype "passive"))
      (node (ref "R90") (pin "1") (pinfunction "1_1") (pintype "passive"))
    )
    (net (code "56") (name "Net-(IC11D--IN)") (class "Default")
      (node (ref "C45") (pin "1") (pinfunction "1_1") (pintype "passive"))
      (node (ref "IC11") (pin "13") (pinfunction "-IN_13") (pintype "input"))
      (node (ref "R85") (pin "1") (pinfunction "1_1") (pintype "passive"))
      (node (ref "R86") (pin "2") (pinfunction "2_2") (pintype "passive"))
      (node (ref "R87") (pin "1") (pinfunction "1_1") (pintype "passive"))
    )
    (net (code "57") (name "Net-(IC12A--IN)") (class "Default")
      (node (ref "C48") (pin "1") (pinfunction "1_1") (pintype "passive"))
      (node (ref "IC12") (pin "2") (pinfunction "-IN_2") (pintype "input"))
      (node (ref "R94") (pin "1") (pinfunction "1_1") (pintype "passive"))
      (node (ref "R95") (pin "2") (pinfunction "2_2") (pintype "passive"))
      (node (ref "R96") (pin "1") (pinfunction "1_1") (pintype "passive"))
    )
    (net (code "58") (name "Net-(IC12B--IN)") (class "Default")
      (node (ref "C49") (pin "1") (pinfunction "1_1") (pintype "passive"))
      (node (ref "IC12") (pin "6") (pinfunction "-IN_6") (pintype "input"))
      (node (ref "R100") (pin "1") (pinfunction "1_1") (pintype "passive"))
      (node (ref "R98") (pin "1") (pinfunction "1_1") (pintype "passive"))
      (node (ref "R99") (pin "2") (pinfunction "2_2") (pintype "passive"))
    )
    (net (code "59") (name "Net-(IC13A-+IN)") (class "Default")
      (node (ref "C53") (pin "2") (pinfunction "2_2") (pintype "passive"))
      (node (ref "IC13") (pin "3") (pinfunction "+IN_3") (pintype "input"))
      (node (ref "IC13") (pin "6") (pinfunction "-IN_6") (pintype "input"))
      (node (ref "IC13") (pin "7") (pinfunction "OUT_7") (pintype "output"))
    )
    (net (code "60") (name "Net-(IC13A--IN)") (class "Default")
      (node (ref "IC13") (pin "2") (pinfunction "-IN_2") (pintype "input"))
      (node (ref "R104") (pin "2") (pinfunction "2_2") (pintype "passive"))
      (node (ref "R105") (pin "2") (pinfunction "2_2") (pintype "passive"))
    )
    (net (code "61") (name "Net-(IC13A-OUT)") (class "Default")
      (node (ref "IC13") (pin "1") (pinfunction "OUT_1") (pintype "output"))
      (node (ref "R103") (pin "2") (pinfunction "2_2") (pintype "passive"))
      (node (ref "R104") (pin "1") (pinfunction "1_1") (pintype "passive"))
    )
    (net (code "62") (name "Net-(IC13B-+IN)") (class "Default")
      (node (ref "C52") (pin "1") (pinfunction "1_1") (pintype "passive"))
      (node (ref "IC13") (pin "5") (pinfunction "+IN_5") (pintype "input"))
      (node (ref "R102") (pin "1") (pinfunction "1_1") (pintype "passive"))
    )
    (net (code "63") (name "Net-(IC14A--IN)") (class "Default")
      (node (ref "IC14") (pin "2") (pinfunction "-IN_2") (pintype "input"))
      (node (ref "R109") (pin "2") (pinfunction "2_2") (pintype "passive"))
      (node (ref "R110") (pin "1") (pinfunction "1_1") (pintype "passive"))
      (node (ref "R112") (pin "1") (pinfunction "1_1") (pintype "passive"))
    )
    (net (code "64") (name "Net-(IC14A-OUT)") (class "Default")
      (node (ref "IC14") (pin "1") (pinfunction "OUT_1") (pintype "output"))
      (node (ref "R108") (pin "2") (pinfunction "2_2") (pintype "passive"))
      (node (ref "R109") (pin "1") (pinfunction "1_1") (pintype "passive"))
    )
    (net (code "65") (name "Net-(IC14B-+IN)") (class "Default")
      (node (ref "C54") (pin "1") (pinfunction "1_1") (pintype "passive"))
      (node (ref "IC14") (pin "5") (pinfunction "+IN_5") (pintype "input"))
      (node (ref "R107") (pin "1") (pinfunction "1_1") (pintype "passive"))
    )
    (net (code "66") (name "Net-(IC14B--IN)") (class "Default")
      (node (ref "C55") (pin "2") (pinfunction "2_2") (pintype "passive"))
      (node (ref "IC14") (pin "6") (pinfunction "-IN_6") (pintype "input"))
      (node (ref "IC14") (pin "7") (pinfunction "OUT_7") (pintype "output"))
      (node (ref "R110") (pin "2") (pinfunction "2_2") (pintype "passive"))
    )
    (net (code "67") (name "Net-(J1-3)") (class "Default")
      (node (ref "J1") (pin "P3") (pinfunction "3_P3") (pintype "passive"))
      (node (ref "R42") (pin "2") (pinfunction "2_2") (pintype "passive"))
    )
    (net (code "68") (name "Net-(J2-3)") (class "Default")
      (node (ref "J2") (pin "P3") (pinfunction "3_P3") (pintype "passive"))
      (node (ref "R29") (pin "2") (pinfunction "2_2") (pintype "passive"))
    )
    (net (code "69") (name "Net-(J3-3)") (class "Default")
      (node (ref "J3") (pin "P3") (pinfunction "3_P3") (pintype "passive"))
      (node (ref "R32") (pin "2") (pinfunction "2_2") (pintype "passive"))
    )
    (net (code "70") (name "Net-(J4-3)") (class "Default")
      (node (ref "J4") (pin "P3") (pinfunction "3_P3") (pintype "passive"))
      (node (ref "R55") (pin "1") (pinfunction "1_1") (pintype "passive"))
    )
    (net (code "71") (name "Net-(J5-3)") (class "Default")
      (node (ref "J5") (pin "P3") (pinfunction "3_P3") (pintype "passive"))
      (node (ref "R56") (pin "1") (pinfunction "1_1") (pintype "passive"))
    )
    (net (code "72") (name "Net-(J6-3)") (class "Default")
      (node (ref "J6") (pin "P3") (pinfunction "3_P3") (pintype "passive"))
      (node (ref "R39") (pin "2") (pinfunction "2_2") (pintype "passive"))
    )
    (net (code "73") (name "Net-(J7-3)") (class "Default")
      (node (ref "J7") (pin "P3") (pinfunction "3_P3") (pintype "passive"))
      (node (ref "R36") (pin "2") (pinfunction "2_2") (pintype "passive"))
    )
    (net (code "74") (name "Net-(J8-2)") (class "Default")
      (node (ref "J8") (pin "P2") (pinfunction "2_P2") (pintype "passive"))
      (node (ref "R60") (pin "2") (pinfunction "2_2") (pintype "passive"))
    )
    (net (code "75") (name "Net-(J8-3)") (class "Default")
      (node (ref "J8") (pin "P3") (pinfunction "3_P3") (pintype "passive"))
      (node (ref "R44") (pin "2") (pinfunction "2_2") (pintype "passive"))
    )
    (net (code "76") (name "Net-(J9-3)") (class "Default")
      (node (ref "J9") (pin "P3") (pinfunction "3_P3") (pintype "passive"))
      (node (ref "R54") (pin "1") (pinfunction "1_1") (pintype "passive"))
    )
    (net (code "77") (name "Net-(J10-3)") (class "Default")
      (node (ref "J10") (pin "P3") (pinfunction "3_P3") (pintype "passive"))
      (node (ref "Q5") (pin "C") (pinfunction "C_C") (pintype "passive"))
      (node (ref "R50") (pin "2") (pinfunction "2_2") (pintype "passive"))
      (node (ref "R51") (pin "1") (pinfunction "1_1") (pintype "passive"))
    )
    (net (code "78") (name "Net-(J14-3)") (class "Default")
      (node (ref "J14") (pin "P3") (pinfunction "3_P3") (pintype "passive"))
      (node (ref "R71") (pin "1") (pinfunction "1_1") (pintype "passive"))
    )
    (net (code "79") (name "Net-(J15-3)") (class "Default")
      (node (ref "J15") (pin "P3") (pinfunction "3_P3") (pintype "passive"))
      (node (ref "R73") (pin "1") (pinfunction "1_1") (pintype "passive"))
    )
    (net (code "80") (name "Net-(J16-3)") (class "Default")
      (node (ref "J16") (pin "P3") (pinfunction "3_P3") (pintype "passive"))
      (node (ref "R75") (pin "1") (pinfunction "1_1") (pintype "passive"))
    )
    (net (code "81") (name "Net-(J19-3)") (class "Default")
      (node (ref "J19") (pin "P3") (pinfunction "3_P3") (pintype "passive"))
      (node (ref "R94") (pin "2") (pinfunction "2_2") (pintype "passive"))
    )
    (net (code "82") (name "Net-(J20-2)") (class "Default")
      (node (ref "J20") (pin "P2") (pinfunction "2_P2") (pintype "passive"))
      (node (ref "R113") (pin "1") (pinfunction "1_1") (pintype "passive"))
    )
    (net (code "83") (name "Net-(J20-3)") (class "Default")
      (node (ref "J20") (pin "P3") (pinfunction "3_P3") (pintype "passive"))
      (node (ref "R98") (pin "2") (pinfunction "2_2") (pintype "passive"))
    )
    (net (code "84") (name "Net-(J21-3)") (class "Default")
      (node (ref "J21") (pin "P3") (pinfunction "3_P3") (pintype "passive"))
      (node (ref "R82") (pin "2") (pinfunction "2_2") (pintype "passive"))
    )
    (net (code "85") (name "Net-(J22-3)") (class "Default")
      (node (ref "J22") (pin "P3") (pinfunction "3_P3") (pintype "passive"))
      (node (ref "R85") (pin "2") (pinfunction "2_2") (pintype "passive"))
    )
    (net (code "86") (name "Net-(J23-3)") (class "Default")
      (node (ref "J23") (pin "P3") (pinfunction "3_P3") (pintype "passive"))
      (node (ref "R88") (pin "2") (pinfunction "2_2") (pintype "passive"))
    )
    (net (code "87") (name "Net-(J24-2)") (class "Default")
      (node (ref "J24") (pin "P2") (pinfunction "2_P2") (pintype "passive"))
      (node (ref "R114") (pin "2") (pinfunction "2_2") (pintype "passive"))
    )
    (net (code "88") (name "Net-(J24-3)") (class "Default")
      (node (ref "J24") (pin "P3") (pinfunction "3_P3") (pintype "passive"))
      (node (ref "R91") (pin "2") (pinfunction "2_2") (pintype "passive"))
    )
    (net (code "89") (name "Net-(LED1-GRN)") (class "Default")
      (node (ref "LED1") (pin "1") (pinfunction "GRN_1") (pintype "bidirectional"))
      (node (ref "R2") (pin "2") (pinfunction "2_2") (pintype "passive"))
    )
    (net (code "90") (name "Net-(LED1-RED)") (class "Default")
      (node (ref "LED1") (pin "3") (pinfunction "RED_3") (pintype "bidirectional"))
      (node (ref "R3") (pin "2") (pinfunction "2_2") (pintype "passive"))
    )
    (net (code "91") (name "Net-(LED2-GRN)") (class "Default")
      (node (ref "LED2") (pin "1") (pinfunction "GRN_1") (pintype "bidirectional"))
      (node (ref "R4") (pin "2") (pinfunction "2_2") (pintype "passive"))
    )
    (net (code "92") (name "Net-(LED2-RED)") (class "Default")
      (node (ref "LED2") (pin "3") (pinfunction "RED_3") (pintype "bidirectional"))
      (node (ref "R7") (pin "2") (pinfunction "2_2") (pintype "passive"))
    )
    (net (code "93") (name "Net-(LED3-GRN)") (class "Default")
      (node (ref "LED3") (pin "1") (pinfunction "GRN_1") (pintype "bidirectional"))
      (node (ref "R9") (pin "2") (pinfunction "2_2") (pintype "passive"))
    )
    (net (code "94") (name "Net-(LED3-RED)") (class "Default")
      (node (ref "LED3") (pin "3") (pinfunction "RED_3") (pintype "bidirectional"))
      (node (ref "R10") (pin "2") (pinfunction "2_2") (pintype "passive"))
    )
    (net (code "95") (name "Net-(LED4-GRN)") (class "Default")
      (node (ref "LED4") (pin "1") (pinfunction "GRN_1") (pintype "bidirectional"))
      (node (ref "R66") (pin "2") (pinfunction "2_2") (pintype "passive"))
    )
    (net (code "96") (name "Net-(LED4-RED)") (class "Default")
      (node (ref "LED4") (pin "3") (pinfunction "RED_3") (pintype "bidirectional"))
      (node (ref "R65") (pin "2") (pinfunction "2_2") (pintype "passive"))
    )
    (net (code "97") (name "Net-(LED5-GRN)") (class "Default")
      (node (ref "LED5") (pin "1") (pinfunction "GRN_1") (pintype "bidirectional"))
      (node (ref "R68") (pin "2") (pinfunction "2_2") (pintype "passive"))
    )
    (net (code "98") (name "Net-(LED5-RED)") (class "Default")
      (node (ref "LED5") (pin "3") (pinfunction "RED_3") (pintype "bidirectional"))
      (node (ref "R67") (pin "2") (pinfunction "2_2") (pintype "passive"))
    )
    (net (code "99") (name "Net-(LED6-GRN)") (class "Default")
      (node (ref "LED6") (pin "1") (pinfunction "GRN_1") (pintype "bidirectional"))
      (node (ref "R70") (pin "2") (pinfunction "2_2") (pintype "passive"))
    )
    (net (code "100") (name "Net-(LED6-RED)") (class "Default")
      (node (ref "LED6") (pin "3") (pinfunction "RED_3") (pintype "bidirectional"))
      (node (ref "R69") (pin "2") (pinfunction "2_2") (pintype "passive"))
    )
    (net (code "101") (name "Net-(Q2-PadB)") (class "Default")
      (node (ref "Q2") (pin "B") (pinfunction "B_B") (pintype "passive"))
      (node (ref "R55") (pin "2") (pinfunction "2_2") (pintype "passive"))
    )
    (net (code "102") (name "Net-(Q3-PadB)") (class "Default")
      (node (ref "Q3") (pin "B") (pinfunction "B_B") (pintype "passive"))
      (node (ref "R54") (pin "2") (pinfunction "2_2") (pintype "passive"))
    )
    (net (code "103") (name "Net-(Q4-PadB)") (class "Default")
      (node (ref "Q4") (pin "B") (pinfunction "B_B") (pintype "passive"))
      (node (ref "R56") (pin "2") (pinfunction "2_2") (pintype "passive"))
    )
    (net (code "104") (name "Net-(Q5-PadB)") (class "Default")
      (node (ref "Q5") (pin "B") (pinfunction "B_B") (pintype "passive"))
      (node (ref "R57") (pin "2") (pinfunction "2_2") (pintype "passive"))
    )
    (net (code "105") (name "Net-(Q6-PadB)") (class "Default")
      (node (ref "Q6") (pin "B") (pinfunction "B_B") (pintype "passive"))
      (node (ref "R58") (pin "2") (pinfunction "2_2") (pintype "passive"))
    )
    (net (code "106") (name "Net-(Q8-PadB)") (class "Default")
      (node (ref "Q8") (pin "B") (pinfunction "B_B") (pintype "passive"))
      (node (ref "R1") (pin "2") (pinfunction "2_2") (pintype "passive"))
    )
    (net (code "107") (name "Net-(Q9-PadB)") (class "Default")
      (node (ref "Q9") (pin "B") (pinfunction "B_B") (pintype "passive"))
      (node (ref "R62") (pin "2") (pinfunction "2_2") (pintype "passive"))
    )
    (net (code "108") (name "Net-(Q10-PadB)") (class "Default")
      (node (ref "Q10") (pin "B") (pinfunction "B_B") (pintype "passive"))
      (node (ref "R71") (pin "2") (pinfunction "2_2") (pintype "passive"))
    )
    (net (code "109") (name "Net-(Q11-PadB)") (class "Default")
      (node (ref "Q11") (pin "B") (pinfunction "B_B") (pintype "passive"))
      (node (ref "R73") (pin "2") (pinfunction "2_2") (pintype "passive"))
    )
    (net (code "110") (name "Net-(Q12-PadB)") (class "Default")
      (node (ref "Q12") (pin "B") (pinfunction "B_B") (pintype "passive"))
      (node (ref "R75") (pin "2") (pinfunction "2_2") (pintype "passive"))
    )
    (net (code "111") (name "Net-(R5-E)") (class "Default")
      (node (ref "R5") (pin "P$1") (pinfunction "E_P$1") (pintype "passive"))
      (node (ref "R8") (pin "2") (pinfunction "2_2") (pintype "passive"))
    )
    (net (code "112") (name "Net-(R5-S)") (class "Default")
      (node (ref "R38") (pin "2") (pinfunction "2_2") (pintype "passive"))
      (node (ref "R5") (pin "P$2") (pinfunction "S_P$2") (pintype "passive"))
    )
    (net (code "113") (name "Net-(R17-S)") (class "Default")
      (node (ref "R17") (pin "P$2") (pinfunction "S_P$2") (pintype "passive"))
      (node (ref "R41") (pin "2") (pinfunction "2_2") (pintype "passive"))
    )
    (net (code "114") (name "Net-(R18-S)") (class "Default")
      (node (ref "R18") (pin "P$2") (pinfunction "S_P$2") (pintype "passive"))
      (node (ref "R30") (pin "2") (pinfunction "2_2") (pintype "passive"))
    )
    (net (code "115") (name "Net-(R19-S)") (class "Default")
      (node (ref "R19") (pin "P$2") (pinfunction "S_P$2") (pintype "passive"))
      (node (ref "R31") (pin "2") (pinfunction "2_2") (pintype "passive"))
    )
    (net (code "116") (name "Net-(R59-A)") (class "Default")
      (node (ref "R21") (pin "2") (pinfunction "2_2") (pintype "passive"))
      (node (ref "R59") (pin "1") (pinfunction "A_1") (pintype "passive"))
    )
    (net (code "117") (name "Net-(R77-S)") (class "Default")
      (node (ref "R77") (pin "P$2") (pinfunction "S_P$2") (pintype "passive"))
      (node (ref "R84") (pin "2") (pinfunction "2_2") (pintype "passive"))
    )
    (net (code "118") (name "Net-(R78-E)") (class "Default")
      (node (ref "R78") (pin "P$1") (pinfunction "E_P$1") (pintype "passive"))
      (node (ref "R97") (pin "2") (pinfunction "2_2") (pintype "passive"))
    )
    (net (code "119") (name "Net-(R78-S)") (class "Default")
      (node (ref "R78") (pin "P$2") (pinfunction "S_P$2") (pintype "passive"))
      (node (ref "R96") (pin "2") (pinfunction "2_2") (pintype "passive"))
    )
    (net (code "120") (name "Net-(R80-S)") (class "Default")
      (node (ref "R80") (pin "P$2") (pinfunction "S_P$2") (pintype "passive"))
      (node (ref "R90") (pin "2") (pinfunction "2_2") (pintype "passive"))
    )
    (net (code "121") (name "Net-(R81-S)") (class "Default")
      (node (ref "R81") (pin "P$2") (pinfunction "S_P$2") (pintype "passive"))
      (node (ref "R87") (pin "2") (pinfunction "2_2") (pintype "passive"))
    )
    (net (code "122") (name "Net-(R111-A)") (class "Default")
      (node (ref "R111") (pin "1") (pinfunction "A_1") (pintype "passive"))
      (node (ref "R112") (pin "2") (pinfunction "2_2") (pintype "passive"))
    )
    (net (code "123") (name "Net-(U1A-+IN)") (class "Default")
      (node (ref "D7") (pin "A") (pinfunction "A_A") (pintype "passive"))
      (node (ref "D8") (pin "A") (pinfunction "A_A") (pintype "passive"))
      (node (ref "R120") (pin "1") (pinfunction "1_1") (pintype "passive"))
      (node (ref "U1") (pin "3") (pinfunction "+IN_3") (pintype "input"))
    )
    (net (code "124") (name "Net-(U1A--IN)") (class "Default")
      (node (ref "D5") (pin "A") (pinfunction "A_A") (pintype "passive"))
      (node (ref "R122") (pin "1") (pinfunction "1_1") (pintype "passive"))
      (node (ref "U1") (pin "2") (pinfunction "-IN_2") (pintype "input"))
    )
    (net (code "125") (name "Net-(U1A-OUT)") (class "Default")
      (node (ref "D5") (pin "C") (pinfunction "C_C") (pintype "passive"))
      (node (ref "R121") (pin "2") (pinfunction "2_2") (pintype "passive"))
      (node (ref "U1") (pin "1") (pinfunction "OUT_1") (pintype "output"))
    )
    (net (code "126") (name "Net-(U1B-+IN)") (class "Default")
      (node (ref "D10") (pin "C") (pinfunction "C_C") (pintype "passive"))
      (node (ref "D9") (pin "C") (pinfunction "C_C") (pintype "passive"))
      (node (ref "R118") (pin "1") (pinfunction "1_1") (pintype "passive"))
      (node (ref "U1") (pin "5") (pinfunction "+IN_5") (pintype "input"))
    )
    (net (code "127") (name "Net-(U1B--IN)") (class "Default")
      (node (ref "D6") (pin "C") (pinfunction "C_C") (pintype "passive"))
      (node (ref "R123") (pin "1") (pinfunction "1_1") (pintype "passive"))
      (node (ref "U1") (pin "6") (pinfunction "-IN_6") (pintype "input"))
    )
    (net (code "128") (name "Net-(U1B-OUT)") (class "Default")
      (node (ref "D6") (pin "A") (pinfunction "A_A") (pintype "passive"))
      (node (ref "R119") (pin "2") (pinfunction "2_2") (pintype "passive"))
      (node (ref "U1") (pin "7") (pinfunction "OUT_7") (pintype "output"))
    )
    (net (code "129") (name "Net-(UC1-PB4{slash}NJTRST)") (class "Default")
      (node (ref "R2") (pin "1") (pinfunction "1_1") (pintype "passive"))
      (node (ref "UC1") (pin "40") (pinfunction "PB4/NJTRST_40") (pintype "bidirectional"))
    )
    (net (code "130") (name "Net-(UC1-PB5{slash}I2C1_SMBA)") (class "Default")
      (node (ref "R3") (pin "1") (pinfunction "1_1") (pintype "passive"))
      (node (ref "UC1") (pin "41") (pinfunction "PB5/I2C1_SMBA_41") (pintype "input"))
    )
    (net (code "131") (name "Net-(UC1-PB6{slash}I2C1_SCL{slash}TIM4_CH1)") (class "Default")
      (node (ref "R4") (pin "1") (pinfunction "1_1") (pintype "passive"))
      (node (ref "UC1") (pin "42") (pinfunction "PB6/I2C1_SCL/TIM4_CH1_42") (pintype "input"))
    )
    (net (code "132") (name "Net-(UC1-PB7{slash}I2C1_SDA{slash}TIM4_CH2)") (class "Default")
      (node (ref "R7") (pin "1") (pinfunction "1_1") (pintype "passive"))
      (node (ref "UC1") (pin "43") (pinfunction "PB7/I2C1_SDA/TIM4_CH2_43") (pintype "bidirectional"))
    )
    (net (code "133") (name "Net-(UC1-PB8{slash}TIM4_CH3)") (class "Default")
      (node (ref "R9") (pin "1") (pinfunction "1_1") (pintype "passive"))
      (node (ref "UC1") (pin "45") (pinfunction "PB8/TIM4_CH3_45") (pintype "bidirectional"))
    )
    (net (code "134") (name "Net-(UC1-PB9{slash}TIM4_CH4)") (class "Default")
      (node (ref "R10") (pin "1") (pinfunction "1_1") (pintype "passive"))
      (node (ref "UC1") (pin "46") (pinfunction "PB9/TIM4_CH4_46") (pintype "input"))
    )
    (net (code "135") (name "Net-(UC1-PD0-OSC_IN)") (class "Default")
      (node (ref "C2") (pin "2") (pinfunction "2_2") (pintype "passive"))
      (node (ref "Q1") (pin "2") (pinfunction "2_2") (pintype "passive"))
      (node (ref "UC1") (pin "5") (pinfunction "PD0-OSC_IN_5") (pintype "input"))
    )
    (net (code "136") (name "Net-(UC1-PD1-OSC_OUT)") (class "Default")
      (node (ref "C17") (pin "2") (pinfunction "2_2") (pintype "passive"))
      (node (ref "Q1") (pin "1") (pinfunction "1_1") (pintype "passive"))
      (node (ref "UC1") (pin "6") (pinfunction "PD1-OSC_OUT_6") (pintype "input"))
    )
    (net (code "137") (name "Net-(UC2-PB4{slash}NJTRST)") (class "Default")
      (node (ref "R70") (pin "1") (pinfunction "1_1") (pintype "passive"))
      (node (ref "UC2") (pin "40") (pinfunction "PB4/NJTRST_40") (pintype "bidirectional"))
    )
    (net (code "138") (name "Net-(UC2-PB5{slash}I2C1_SMBA)") (class "Default")
      (node (ref "R69") (pin "1") (pinfunction "1_1") (pintype "passive"))
      (node (ref "UC2") (pin "41") (pinfunction "PB5/I2C1_SMBA_41") (pintype "input"))
    )
    (net (code "139") (name "Net-(UC2-PB6{slash}I2C1_SCL{slash}TIM4_CH1)") (class "Default")
      (node (ref "R68") (pin "1") (pinfunction "1_1") (pintype "passive"))
      (node (ref "UC2") (pin "42") (pinfunction "PB6/I2C1_SCL/TIM4_CH1_42") (pintype "input"))
    )
    (net (code "140") (name "Net-(UC2-PB7{slash}I2C1_SDA{slash}TIM4_CH2)") (class "Default")
      (node (ref "R67") (pin "1") (pinfunction "1_1") (pintype "passive"))
      (node (ref "UC2") (pin "43") (pinfunction "PB7/I2C1_SDA/TIM4_CH2_43") (pintype "bidirectional"))
    )
    (net (code "141") (name "Net-(UC2-PB8{slash}TIM4_CH3)") (class "Default")
      (node (ref "R66") (pin "1") (pinfunction "1_1") (pintype "passive"))
      (node (ref "UC2") (pin "45") (pinfunction "PB8/TIM4_CH3_45") (pintype "bidirectional"))
    )
    (net (code "142") (name "Net-(UC2-PB9{slash}TIM4_CH4)") (class "Default")
      (node (ref "R65") (pin "1") (pinfunction "1_1") (pintype "passive"))
      (node (ref "UC2") (pin "46") (pinfunction "PB9/TIM4_CH4_46") (pintype "input"))
    )
    (net (code "143") (name "Net-(UC2-PD0-OSC_IN)") (class "Default")
      (node (ref "C36") (pin "2") (pinfunction "2_2") (pintype "passive"))
      (node (ref "Q7") (pin "2") (pinfunction "2_2") (pintype "passive"))
      (node (ref "UC2") (pin "5") (pinfunction "PD0-OSC_IN_5") (pintype "input"))
    )
    (net (code "144") (name "Net-(UC2-PD1-OSC_OUT)") (class "Default")
      (node (ref "C35") (pin "2") (pinfunction "2_2") (pintype "passive"))
      (node (ref "Q7") (pin "1") (pinfunction "1_1") (pintype "passive"))
      (node (ref "UC2") (pin "6") (pinfunction "PD1-OSC_OUT_6") (pintype "input"))
    )
    (net (code "145") (name "OUT_1") (class "Default")
      (node (ref "D10") (pin "A") (pinfunction "A_A") (pintype "passive"))
      (node (ref "D7") (pin "C") (pinfunction "C_C") (pintype "passive"))
      (node (ref "R117") (pin "P$3") (pinfunction "A_P$3") (pintype "passive"))
      (node (ref "UNI-BI") (pin "2") (pinfunction "P_2") (pintype "passive"))
    )
    (net (code "146") (name "OUT_2") (class "Default")
      (node (ref "D8") (pin "C") (pinfunction "C_C") (pintype "passive"))
      (node (ref "D9") (pin "A") (pinfunction "A_A") (pintype "passive"))
      (node (ref "R117") (pin "P$1") (pinfunction "E_P$1") (pintype "passive"))
      (node (ref "UNI-BI") (pin "5") (pinfunction "P1_5") (pintype "passive"))
    )
    (net (code "147") (name "OUT_BI1") (class "Default")
      (node (ref "J13") (pin "P3") (pinfunction "3_P3") (pintype "passive"))
      (node (ref "R22") (pin "1") (pinfunction "1_1") (pintype "passive"))
      (node (ref "UNI-BI") (pin "1") (pinfunction "O_1") (pintype "passive"))
    )
    (net (code "148") (name "OUT_BI2") (class "Default")
      (node (ref "FM-A") (pin "1") (pinfunction "O_1") (pintype "passive"))
      (node (ref "J26") (pin "P3") (pinfunction "3_P3") (pintype "passive"))
      (node (ref "R108") (pin "1") (pinfunction "1_1") (pintype "passive"))
      (node (ref "UNI-BI") (pin "4") (pinfunction "O1_4") (pintype "passive"))
    )
    (net (code "149") (name "OUT_UNI1") (class "Default")
      (node (ref "J12") (pin "P3") (pinfunction "3_P3") (pintype "passive"))
      (node (ref "R24") (pin "1") (pinfunction "1_1") (pintype "passive"))
      (node (ref "UNI-BI") (pin "3") (pinfunction "S_3") (pintype "passive"))
    )
    (net (code "150") (name "OUT_UNI2") (class "Default")
      (node (ref "J25") (pin "P3") (pinfunction "3_P3") (pintype "passive"))
      (node (ref "R103") (pin "1") (pinfunction "1_1") (pintype "passive"))
      (node (ref "UNI-BI") (pin "6") (pinfunction "S1_6") (pintype "passive"))
    )
    (net (code "151") (name "PROC_ADC") (class "Default")
      (node (ref "C28") (pin "2") (pinfunction "2_2") (pintype "passive"))
      (node (ref "C46") (pin "2") (pinfunction "2_2") (pintype "passive"))
      (node (ref "IC11") (pin "8") (pinfunction "OUT_8") (pintype "output"))
      (node (ref "IC9") (pin "8") (pinfunction "OUT_8") (pintype "output"))
      (node (ref "R33") (pin "1") (pinfunction "1_1") (pintype "passive"))
      (node (ref "R89") (pin "1") (pinfunction "1_1") (pintype "passive"))
      (node (ref "UC1") (pin "17") (pinfunction "PA7/SPI1_MOSI/ADC12_IN7/TIM3_CH2_17") (pintype "bidirectional"))
      (node (ref "UC2") (pin "17") (pinfunction "PA7/SPI1_MOSI/ADC12_IN7/TIM3_CH2_17") (pintype "bidirectional"))
    )
    (net (code "152") (name "RANGE_SW") (class "Default")
      (node (ref "SW1") (pin "3") (pinfunction "S_3") (pintype "passive"))
      (node (ref "SW1") (pin "4") (pinfunction "S1_4") (pintype "passive"))
      (node (ref "SW4") (pin "3") (pinfunction "S_3") (pintype "passive"))
      (node (ref "SW4") (pin "4") (pinfunction "S1_4") (pintype "passive"))
      (node (ref "UC1") (pin "11") (pinfunction "PA1/USART2_RTS/ADC12_IN1/TIM2_CH2_11") (pintype "bidirectional"))
      (node (ref "UC2") (pin "11") (pinfunction "PA1/USART2_RTS/ADC12_IN1/TIM2_CH2_11") (pintype "bidirectional"))
    )
    (net (code "153") (name "RESET") (class "Default")
      (node (ref "JTAG") (pin "10") (pinfunction "10_10") (pintype "passive"))
      (node (ref "JTAG1") (pin "10") (pinfunction "10_10") (pintype "passive"))
      (node (ref "UC1") (pin "7") (pinfunction "NRST_7") (pintype "input"))
      (node (ref "UC2") (pin "7") (pinfunction "NRST_7") (pintype "input"))
    )
    (net (code "154") (name "RX") (class "Default")
      (node (ref "UC1") (pin "31") (pinfunction "PA10/USART1_RX/TIM1_CH3_31") (pintype "bidirectional"))
      (node (ref "UC2") (pin "31") (pinfunction "PA10/USART1_RX/TIM1_CH3_31") (pintype "bidirectional"))
    )
    (net (code "155") (name "SHAPE_ADC") (class "Default")
      (node (ref "C32") (pin "2") (pinfunction "2_2") (pintype "passive"))
      (node (ref "C44") (pin "2") (pinfunction "2_2") (pintype "passive"))
      (node (ref "IC11") (pin "1") (pinfunction "OUT_1") (pintype "output"))
      (node (ref "IC9") (pin "1") (pinfunction "OUT_1") (pintype "output"))
      (node (ref "R40") (pin "1") (pinfunction "1_1") (pintype "passive"))
      (node (ref "R83") (pin "1") (pinfunction "1_1") (pintype "passive"))
      (node (ref "UC1") (pin "15") (pinfunction "PA5/SPI1_SCK/ADC12_IN5_15") (pintype "bidirectional"))
      (node (ref "UC2") (pin "15") (pinfunction "PA5/SPI1_SCK/ADC12_IN5_15") (pintype "bidirectional"))
    )
    (net (code "156") (name "START") (class "Default")
      (node (ref "Q10") (pin "C") (pinfunction "C_C") (pintype "passive"))
      (node (ref "Q2") (pin "C") (pinfunction "C_C") (pintype "passive"))
      (node (ref "R47") (pin "1") (pinfunction "1_1") (pintype "passive"))
      (node (ref "R72") (pin "1") (pinfunction "1_1") (pintype "passive"))
      (node (ref "UC1") (pin "22") (pinfunction "PB11/I2C2_SDA/USART3_RX_22") (pintype "input"))
      (node (ref "UC2") (pin "22") (pinfunction "PB11/I2C2_SDA/USART3_RX_22") (pintype "input"))
    )
    (net (code "157") (name "TRIGGIN_A") (class "Default")
      (node (ref "J4") (pin "P2") (pinfunction "2_P2") (pintype "passive"))
      (node (ref "SYNC-A") (pin "2") (pinfunction "P_2") (pintype "passive"))
    )
    (net (code "158") (name "TRIGGIN_B") (class "Default")
      (node (ref "J14") (pin "P2") (pinfunction "2_P2") (pintype "passive"))
      (node (ref "SYNC-B") (pin "COM") (pinfunction "COMMON_COM") (pintype "passive"))
    )
    (net (code "159") (name "TX") (class "Default")
      (node (ref "UC1") (pin "30") (pinfunction "PA9/USART1_TX/TIM1_CH2_30") (pintype "input"))
      (node (ref "UC2") (pin "30") (pinfunction "PA9/USART1_TX/TIM1_CH2_30") (pintype "input"))
    )
    (net (code "160") (name "UNI") (class "Default")
      (node (ref "IC10") (pin "4") (pinfunction "OUTA_4") (pintype "output"))
      (node (ref "IC4") (pin "4") (pinfunction "OUTA_4") (pintype "output"))
      (node (ref "R101") (pin "2") (pinfunction "2_2") (pintype "passive"))
      (node (ref "R14") (pin "2") (pinfunction "2_2") (pintype "passive"))
    )
    (net (code "161") (name "VCC") (class "Default")
      (node (ref "C18") (pin "1") (pinfunction "1_1") (pintype "passive"))
      (node (ref "C20") (pin "1") (pinfunction "1_1") (pintype "passive"))
      (node (ref "C3") (pin "1") (pinfunction "1_1") (pintype "passive"))
      (node (ref "C56") (pin "1") (pinfunction "1_1") (pintype "passive"))
      (node (ref "C57") (pin "1") (pinfunction "1_1") (pintype "passive"))
      (node (ref "C61") (pin "+") (pinfunction "+_+") (pintype "passive"))
      (node (ref "C65") (pin "+") (pinfunction "+_+") (pintype "passive"))
      (node (ref "C8") (pin "+") (pinfunction "+_+") (pintype "passive"))
      (node (ref "D3") (pin "C") (pinfunction "C_C") (pintype "passive"))
      (node (ref "IC1") (pin "3") (pinfunction "VIN_3") (pintype "input"))
      (node (ref "IC13") (pin "8") (pinfunction "V+_8") (pintype "power_in"))
      (node (ref "IC14") (pin "8") (pinfunction "V+_8") (pintype "power_in"))
      (node (ref "IC16") (pin "3") (pinfunction "VIN_3") (pintype "input"))
      (node (ref "IC17") (pin "3") (pinfunction "VIN_3") (pintype "input"))
      (node (ref "IC3") (pin "3") (pinfunction "VIN_3") (pintype "input"))
      (node (ref "IC5") (pin "8") (pinfunction "V+_8") (pintype "power_in"))
      (node (ref "IC6") (pin "8") (pinfunction "V+_8") (pintype "power_in"))
      (node (ref "R11") (pin "2") (pinfunction "2_2") (pintype "passive"))
      (node (ref "R114") (pin "1") (pinfunction "1_1") (pintype "passive"))
      (node (ref "R120") (pin "2") (pinfunction "2_2") (pintype "passive"))
      (node (ref "R122") (pin "2") (pinfunction "2_2") (pintype "passive"))
      (node (ref "R51") (pin "2") (pinfunction "2_2") (pintype "passive"))
      (node (ref "R53") (pin "2") (pinfunction "2_2") (pintype "passive"))
      (node (ref "R60") (pin "1") (pinfunction "1_1") (pintype "passive"))
      (node (ref "R63") (pin "2") (pinfunction "2_2") (pintype "passive"))
      (node (ref "U1") (pin "8") (pinfunction "V+_8") (pintype "power_in"))
    )
    (net (code "162") (name "VEE") (class "Default")
      (node (ref "C10") (pin "2") (pinfunction "2_2") (pintype "passive"))
      (node (ref "C24") (pin "2") (pinfunction "2_2") (pintype "passive"))
      (node (ref "C25") (pin "2") (pinfunction "2_2") (pintype "passive"))
      (node (ref "C58") (pin "2") (pinfunction "2_2") (pintype "passive"))
      (node (ref "C59") (pin "2") (pinfunction "2_2") (pintype "passive"))
      (node (ref "C62") (pin "-") (pinfunction "-_-") (pintype "passive"))
      (node (ref "D4") (pin "A") (pinfunction "A_A") (pintype "passive"))
      (node (ref "IC13") (pin "4") (pinfunction "V-_4") (pintype "power_in"))
      (node (ref "IC14") (pin "4") (pinfunction "V-_4") (pintype "power_in"))
      (node (ref "IC5") (pin "4") (pinfunction "V-_4") (pintype "power_in"))
      (node (ref "IC6") (pin "4") (pinfunction "V-_4") (pintype "power_in"))
      (node (ref "R115") (pin "1") (pinfunction "1_1") (pintype "passive"))
      (node (ref "R118") (pin "2") (pinfunction "2_2") (pintype "passive"))
      (node (ref "R123") (pin "2") (pinfunction "2_2") (pintype "passive"))
      (node (ref "R27") (pin "1") (pinfunction "1_1") (pintype "passive"))
      (node (ref "U1") (pin "4") (pinfunction "V-_4") (pintype "power_in"))
    )
    (net (code "163") (name "VOCT_ADC") (class "Default")
      (node (ref "C31") (pin "2") (pinfunction "2_2") (pintype "passive"))
      (node (ref "C48") (pin "2") (pinfunction "2_2") (pintype "passive"))
      (node (ref "IC12") (pin "1") (pinfunction "OUT_1") (pintype "output"))
      (node (ref "IC8") (pin "1") (pinfunction "OUT_1") (pintype "output"))
      (node (ref "R37") (pin "1") (pinfunction "1_1") (pintype "passive"))
      (node (ref "R95") (pin "1") (pinfunction "1_1") (pintype "passive"))
      (node (ref "UC1") (pin "13") (pinfunction "PA3/USART2_RX/ADC12_IN3/TIM2_CH4_13") (pintype "bidirectional"))
      (node (ref "UC2") (pin "13") (pinfunction "PA3/USART2_RX/ADC12_IN3/TIM2_CH4_13") (pintype "bidirectional"))
    )
    (net (code "164") (name "VOCT_IN") (class "Default")
      (node (ref "J19") (pin "P2") (pinfunction "2_P2") (pintype "passive"))
      (node (ref "J30") (pin "P3") (pinfunction "3_P3") (pintype "passive"))
      (node (ref "J6") (pin "P2") (pinfunction "2_P2") (pintype "passive"))
    )
    (net (code "165") (name "unconnected-(J1-2-PadP2)") (class "Default")
      (node (ref "J1") (pin "P2") (pinfunction "2_P2") (pintype "passive"))
    )
    (net (code "166") (name "unconnected-(J2-2-PadP2)") (class "Default")
      (node (ref "J2") (pin "P2") (pinfunction "2_P2") (pintype "passive"))
    )
    (net (code "167") (name "unconnected-(J3-2-PadP2)") (class "Default")
      (node (ref "J3") (pin "P2") (pinfunction "2_P2") (pintype "passive"))
    )
    (net (code "168") (name "unconnected-(J10-2-PadP2)") (class "Default")
      (node (ref "J10") (pin "P2") (pinfunction "2_P2") (pintype "passive"))
    )
    (net (code "169") (name "unconnected-(J11-2-PadP2)") (class "Default")
      (node (ref "J11") (pin "P2") (pinfunction "2_P2") (pintype "passive"))
    )
    (net (code "170") (name "unconnected-(J12-2-PadP2)") (class "Default")
      (node (ref "J12") (pin "P2") (pinfunction "2_P2") (pintype "passive"))
    )
    (net (code "171") (name "unconnected-(J13-2-PadP2)") (class "Default")
      (node (ref "J13") (pin "P2") (pinfunction "2_P2") (pintype "passive"))
    )
    (net (code "172") (name "unconnected-(J17-2-PadP2)") (class "Default")
      (node (ref "J17") (pin "P2") (pinfunction "2_P2") (pintype "passive"))
    )
    (net (code "173") (name "unconnected-(J18-2-PadP2)") (class "Default")
      (node (ref "J18") (pin "P2") (pinfunction "2_P2") (pintype "passive"))
    )
    (net (code "174") (name "unconnected-(J21-2-PadP2)") (class "Default")
      (node (ref "J21") (pin "P2") (pinfunction "2_P2") (pintype "passive"))
    )
    (net (code "175") (name "unconnected-(J22-2-PadP2)") (class "Default")
      (node (ref "J22") (pin "P2") (pinfunction "2_P2") (pintype "passive"))
    )
    (net (code "176") (name "unconnected-(J23-2-PadP2)") (class "Default")
      (node (ref "J23") (pin "P2") (pinfunction "2_P2") (pintype "passive"))
    )
    (net (code "177") (name "unconnected-(J25-2-PadP2)") (class "Default")
      (node (ref "J25") (pin "P2") (pinfunction "2_P2") (pintype "passive"))
    )
    (net (code "178") (name "unconnected-(J26-2-PadP2)") (class "Default")
      (node (ref "J26") (pin "P2") (pinfunction "2_P2") (pintype "passive"))
    )
    (net (code "179") (name "unconnected-(J30-2-PadP2)") (class "Default")
      (node (ref "J30") (pin "P2") (pinfunction "2_P2") (pintype "passive"))
    )
    (net (code "180") (name "unconnected-(JTAG-Pad7)") (class "Default")
      (node (ref "JTAG") (pin "7") (pinfunction "7_7") (pintype "passive"))
    )
    (net (code "181") (name "unconnected-(JTAG1-Pad7)") (class "Default")
      (node (ref "JTAG1") (pin "7") (pinfunction "7_7") (pintype "passive"))
    )
    (net (code "182") (name "unconnected-(MAX-2-PadP2)") (class "Default")
      (node (ref "MAX") (pin "P2") (pinfunction "2_P2") (pintype "passive"))
    )
    (net (code "183") (name "unconnected-(MIN-2-PadP2)") (class "Default")
      (node (ref "MIN") (pin "P2") (pinfunction "2_P2") (pintype "passive"))
    )
    (net (code "184") (name "unconnected-(MIX-2-PadP2)") (class "Default")
      (node (ref "MIX") (pin "P2") (pinfunction "2_P2") (pintype "passive"))
    )
    (net (code "185") (name "unconnected-(UC1-PA8{slash}USART1_CK{slash}TIM1_CH1{slash}MCO-Pad29)") (class "Default")
      (node (ref "UC1") (pin "29") (pinfunction "PA8/USART1_CK/TIM1_CH1/MCO_29") (pintype "bidirectional"))
    )
    (net (code "186") (name "unconnected-(UC1-PB14{slash}SPI2_MISO{slash}USART3_RTS{slash}TIM1_CH2N-Pad27)") (class "Default")
      (node (ref "UC1") (pin "27") (pinfunction "PB14/SPI2_MISO/USART3_RTS/TIM1_CH2N_27") (pintype "input"))
    )
    (net (code "187") (name "unconnected-(UC1-PC13-TAMPER-RTC-Pad2)") (class "Default")
      (node (ref "UC1") (pin "2") (pinfunction "PC13-TAMPER-RTC_2") (pintype "input"))
    )
    (net (code "188") (name "unconnected-(UC1-PC14-OSC32_IN-Pad3)") (class "Default")
      (node (ref "UC1") (pin "3") (pinfunction "PC14-OSC32_IN_3") (pintype "input"))
    )
    (net (code "189") (name "unconnected-(UC1-PC15-OSC32_OUT-Pad4)") (class "Default")
      (node (ref "UC1") (pin "4") (pinfunction "PC15-OSC32_OUT_4") (pintype "input"))
    )
    (net (code "190") (name "unconnected-(UC2-PA8{slash}USART1_CK{slash}TIM1_CH1{slash}MCO-Pad29)") (class "Default")
      (node (ref "UC2") (pin "29") (pinfunction "PA8/USART1_CK/TIM1_CH1/MCO_29") (pintype "bidirectional"))
    )
    (net (code "191") (name "unconnected-(UC2-PB14{slash}SPI2_MISO{slash}USART3_RTS{slash}TIM1_CH2N-Pad27)") (class "Default")
      (node (ref "UC2") (pin "27") (pinfunction "PB14/SPI2_MISO/USART3_RTS/TIM1_CH2N_27") (pintype "input"))
    )
    (net (code "192") (name "unconnected-(UC2-PC13-TAMPER-RTC-Pad2)") (class "Default")
      (node (ref "UC2") (pin "2") (pinfunction "PC13-TAMPER-RTC_2") (pintype "input"))
    )
    (net (code "193") (name "unconnected-(UC2-PC14-OSC32_IN-Pad3)") (class "Default")
      (node (ref "UC2") (pin "3") (pinfunction "PC14-OSC32_IN_3") (pintype "input"))
    )
    (net (code "194") (name "unconnected-(UC2-PC15-OSC32_OUT-Pad4)") (class "Default")
      (node (ref "UC2") (pin "4") (pinfunction "PC15-OSC32_OUT_4") (pintype "input"))
    )
  )
)
